# M8650D_cpld.net
KiCad netlist of a schematic drawn in EAGLE
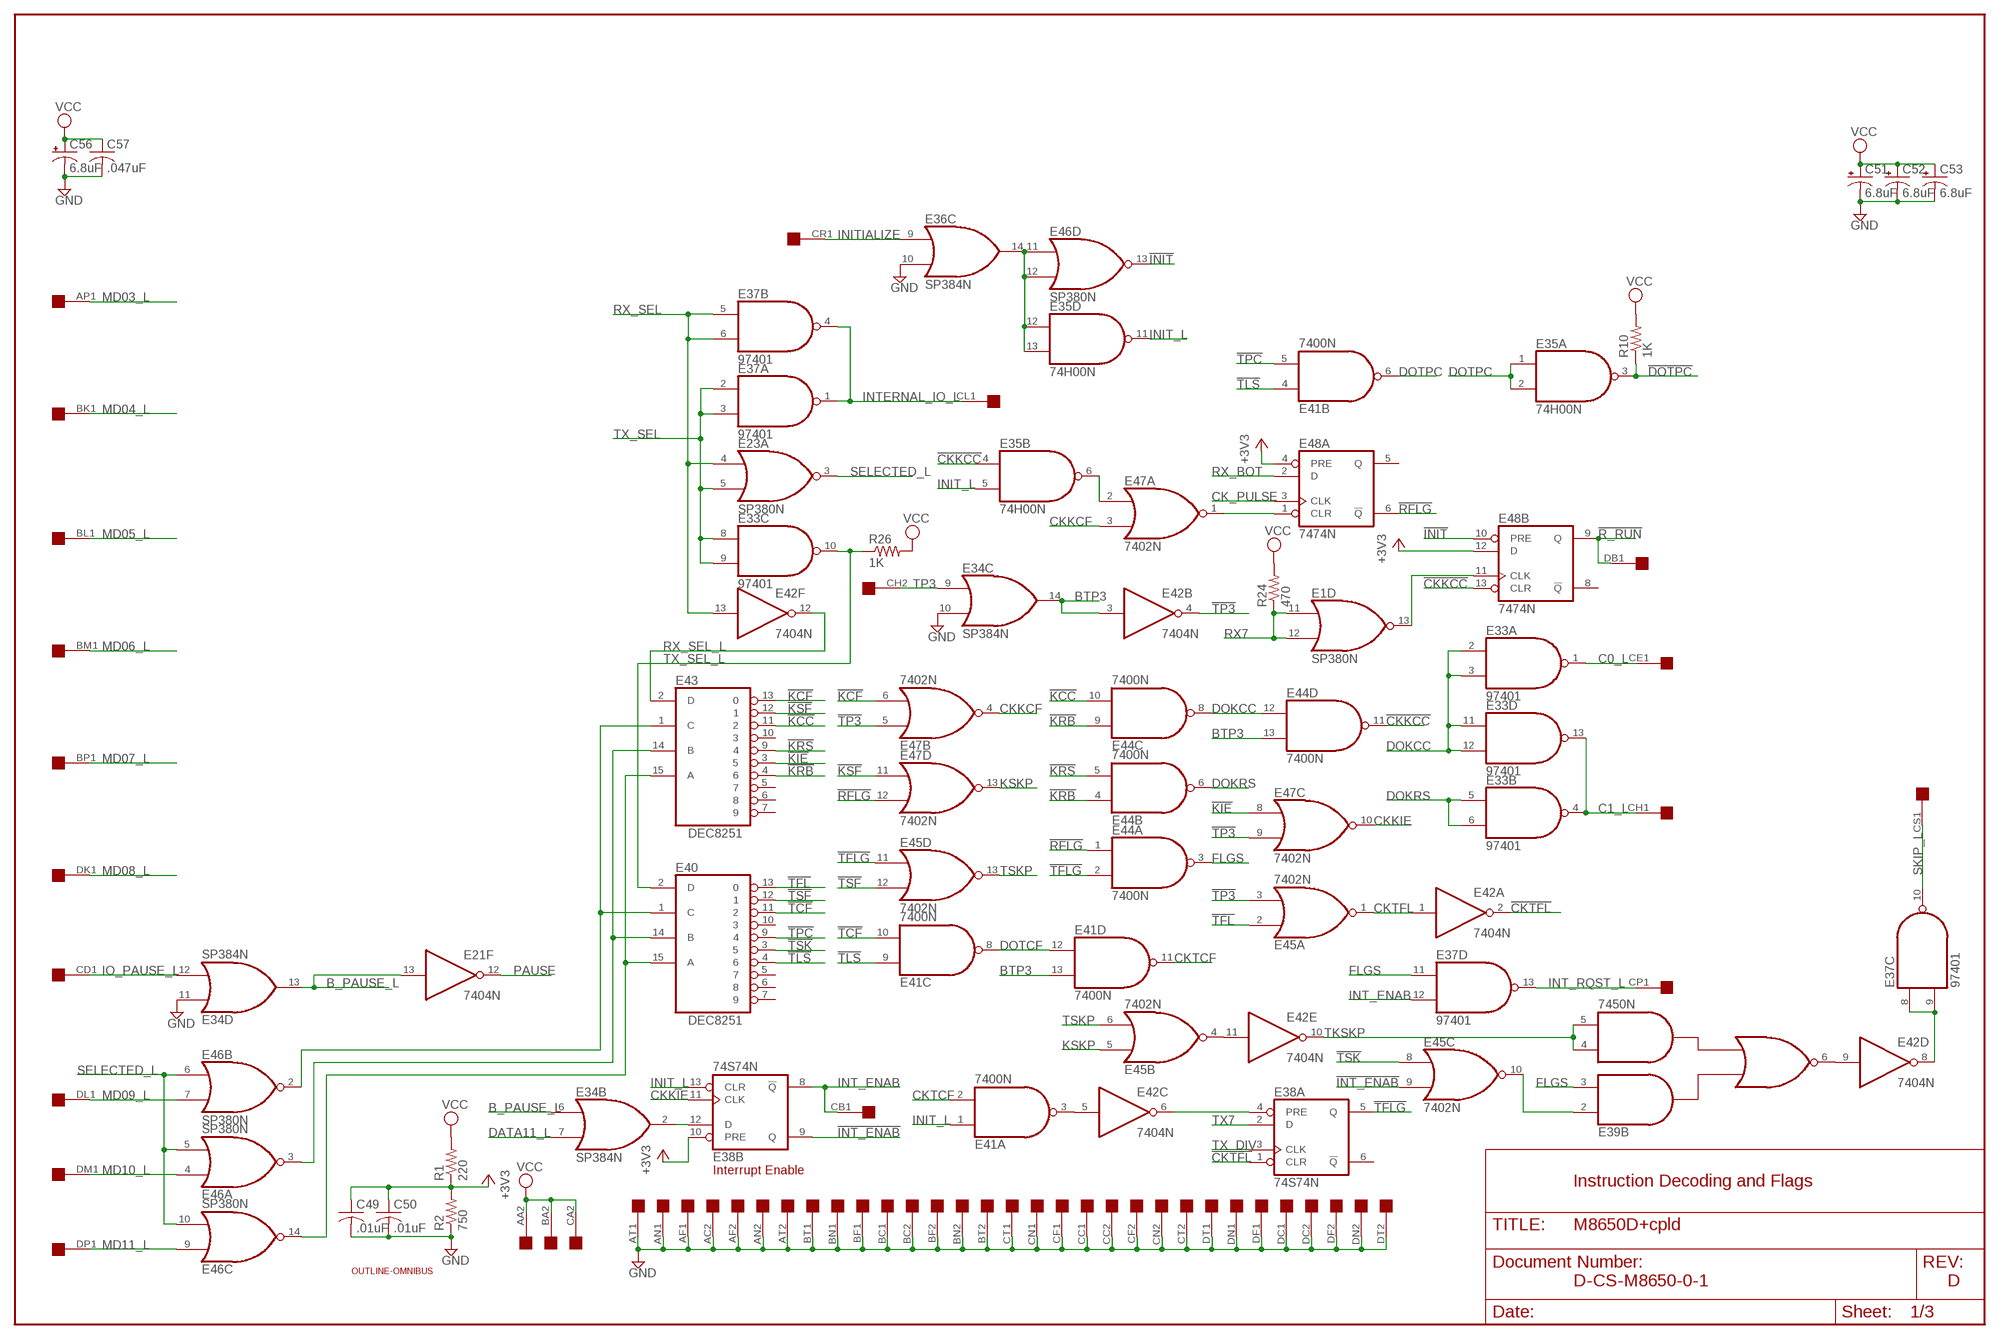
[diagram p0: schematic, sheet 1]
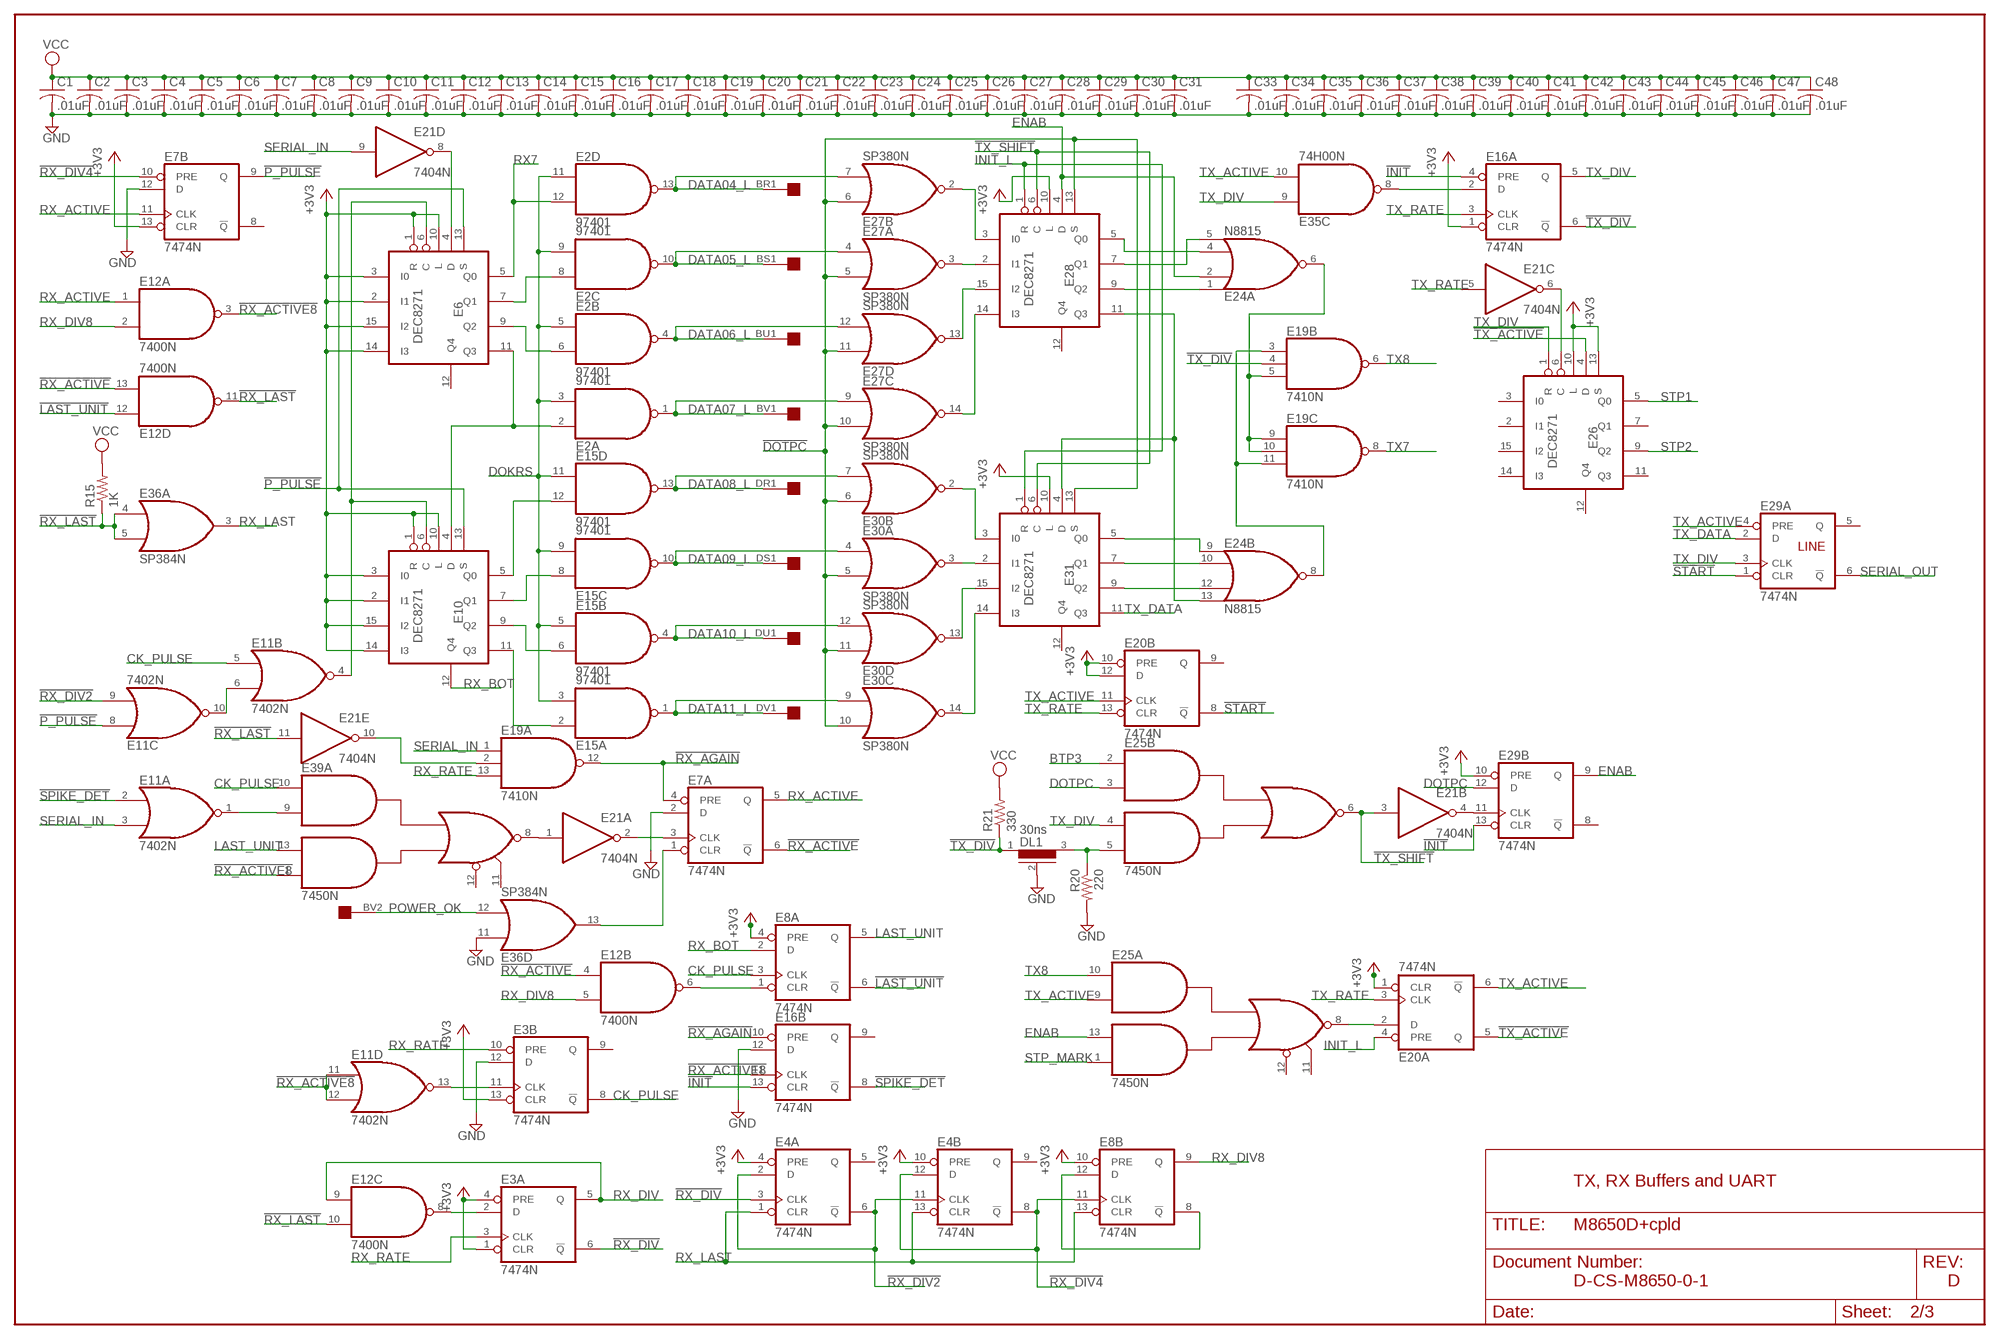
[diagram p1: schematic, sheet 2]
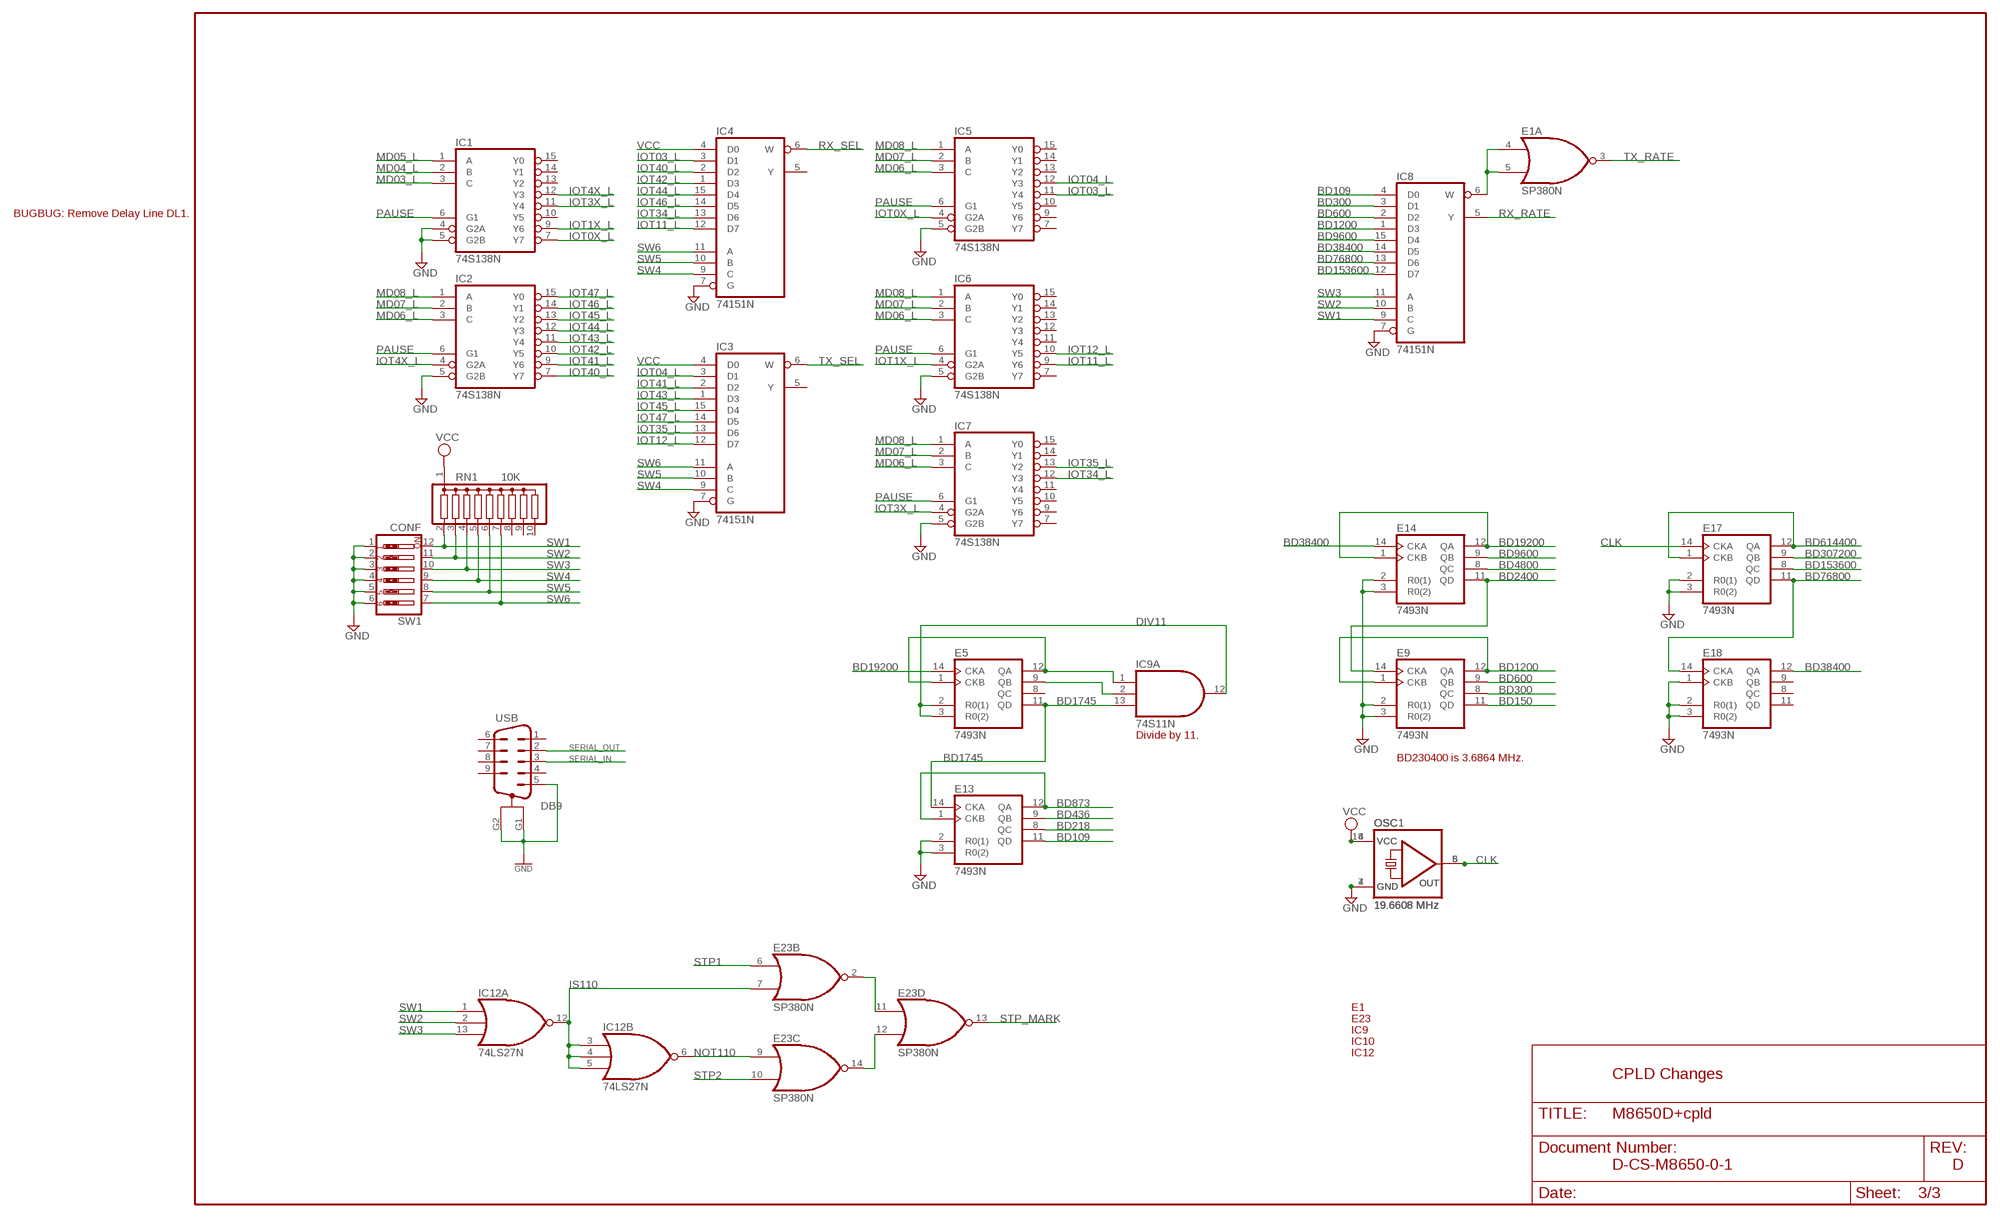
[diagram p2: schematic, sheet 3]

(export (version "E")
  (design (tool "Eeschema 10.0.6"))
  (components
    (comp (ref "E1")
      (value "SP380N")
      (footprint "eagle-import:DIL14")
      (libsource (lib "eagle-import") (part "SP380N"))
    )
    (comp (ref "E5")
      (value "7493N")
      (footprint "eagle-import:DIL14")
      (libsource (lib "eagle-import") (part "7493NLS"))
    )
    (comp (ref "E9")
      (value "7493N")
      (footprint "eagle-import:DIL14")
      (libsource (lib "eagle-import") (part "7493NLS"))
    )
    (comp (ref "E13")
      (value "7493N")
      (footprint "eagle-import:DIL14")
      (libsource (lib "eagle-import") (part "7493NLS"))
    )
    (comp (ref "E14")
      (value "7493N")
      (footprint "eagle-import:DIL14")
      (libsource (lib "eagle-import") (part "7493NLS"))
    )
    (comp (ref "E17")
      (value "7493N")
      (footprint "eagle-import:DIL14")
      (libsource (lib "eagle-import") (part "7493NLS"))
    )
    (comp (ref "E18")
      (value "7493N")
      (footprint "eagle-import:DIL14")
      (libsource (lib "eagle-import") (part "7493NLS"))
    )
    (comp (ref "E23")
      (value "SP380N")
      (footprint "eagle-import:DIL14")
      (libsource (lib "eagle-import") (part "SP380N"))
    )
    (comp (ref "IC1")
      (value "74S138N")
      (footprint "eagle-import:DIL16")
      (libsource (lib "eagle-import") (part "74138NS"))
    )
    (comp (ref "IC2")
      (value "74S138N")
      (footprint "eagle-import:DIL16")
      (libsource (lib "eagle-import") (part "74138NS"))
    )
    (comp (ref "IC3")
      (value "74151N")
      (footprint "eagle-import:DIL16")
      (libsource (lib "eagle-import") (part "74151NS"))
    )
    (comp (ref "IC4")
      (value "74151N")
      (footprint "eagle-import:DIL16")
      (libsource (lib "eagle-import") (part "74151NS"))
    )
    (comp (ref "IC5")
      (value "74S138N")
      (footprint "eagle-import:DIL16")
      (libsource (lib "eagle-import") (part "74138NS"))
    )
    (comp (ref "IC6")
      (value "74S138N")
      (footprint "eagle-import:DIL16")
      (libsource (lib "eagle-import") (part "74138NS"))
    )
    (comp (ref "IC7")
      (value "74S138N")
      (footprint "eagle-import:DIL16")
      (libsource (lib "eagle-import") (part "74138NS"))
    )
    (comp (ref "IC8")
      (value "74151N")
      (footprint "eagle-import:DIL16")
      (libsource (lib "eagle-import") (part "74151N"))
    )
    (comp (ref "IC9")
      (value "74S11N")
      (footprint "eagle-import:DIL14")
      (libsource (lib "eagle-import") (part "7411NS"))
    )
    (comp (ref "IC12")
      (value "74LS27N")
      (footprint "eagle-import:DIL14")
      (libsource (lib "eagle-import") (part "7427NLS"))
    )
    (comp (ref "OSC")
      (value "19.6608 MHz")
      (footprint "eagle-import:DIL08S")
      (libsource (lib "eagle-import") (part "QG5460"))
    )
    (comp (ref "OSC1")
      (value "19.6608 MHz")
      (footprint "eagle-import:DIL14S")
      (libsource (lib "eagle-import") (part "QG5860"))
    )
    (comp (ref "RN1")
      (value "10K")
      (footprint "eagle-import:SIL10")
      (libsource (lib "eagle-import") (part "G09R"))
    )
    (comp (ref "SW1")
      (value "CONF")
      (footprint "eagle-import:EDG-06")
      (libsource (lib "eagle-import") (part "SW_DIP-6"))
    )
    (comp (ref "USB")
      (value "DB9")
      (footprint "eagle-import:AMP_DB-9RA")
      (fields (field (name "MANF") "TE/AMP"))
      (libsource (lib "eagle-import") (part "DB9"))
    )
    (comp (ref "C49")
      (value ".01uF")
      (footprint "eagle-import:C050-025X075")
      (libsource (lib "eagle-import") (part "C-US050-025X075"))
    )
    (comp (ref "C50")
      (value ".01uF")
      (footprint "eagle-import:C050-025X075")
      (libsource (lib "eagle-import") (part "C-US050-025X075"))
    )
    (comp (ref "C51")
      (value "6.8uF")
      (footprint "eagle-import:E12-8")
      (libsource (lib "eagle-import") (part "CPOL-USE20-8AXIAL"))
    )
    (comp (ref "C52")
      (value "6.8uF")
      (footprint "eagle-import:E12-8")
      (libsource (lib "eagle-import") (part "CPOL-USE20-8AXIAL"))
    )
    (comp (ref "C53")
      (value "6.8uF")
      (footprint "eagle-import:E12-8")
      (libsource (lib "eagle-import") (part "CPOL-USE20-8AXIAL"))
    )
    (comp (ref "C56")
      (value "6.8uF")
      (footprint "eagle-import:E12-8")
      (libsource (lib "eagle-import") (part "CPOL-USE20-8AXIAL"))
    )
    (comp (ref "C57")
      (value ".047uF")
      (footprint "eagle-import:C050-025X075")
      (libsource (lib "eagle-import") (part "C-US050-025X075"))
    )
    (comp (ref "E21")
      (value "7404N")
      (footprint "eagle-import:DIL14")
      (libsource (lib "eagle-import") (part "7404N"))
    )
    (comp (ref "E33")
      (value "97401")
      (footprint "eagle-import:DIL14")
      (libsource (lib "eagle-import") (part "7401NLS"))
    )
    (comp (ref "E34")
      (value "SP384N")
      (footprint "eagle-import:DIL14")
      (libsource (lib "eagle-import") (part "SP384N"))
    )
    (comp (ref "E35")
      (value "74H00N")
      (footprint "eagle-import:DIL14")
      (libsource (lib "eagle-import") (part "7400N"))
    )
    (comp (ref "E36")
      (value "SP384N")
      (footprint "eagle-import:DIL14")
      (libsource (lib "eagle-import") (part "SP384N"))
    )
    (comp (ref "E37")
      (value "97401")
      (footprint "eagle-import:DIL14")
      (libsource (lib "eagle-import") (part "7401NLS"))
    )
    (comp (ref "E38")
      (value "74S74N")
      (footprint "eagle-import:DIL14")
      (libsource (lib "eagle-import") (part "7474NS"))
    )
    (comp (ref "E39")
      (value "7450N")
      (footprint "eagle-import:DIL14")
      (libsource (lib "eagle-import") (part "7450N"))
    )
    (comp (ref "E40")
      (value "DEC8251")
      (footprint "eagle-import:DIL16")
      (libsource (lib "eagle-import") (part "DEC8251"))
    )
    (comp (ref "E41")
      (value "7400N")
      (footprint "eagle-import:DIL14")
      (libsource (lib "eagle-import") (part "7400N"))
    )
    (comp (ref "E42")
      (value "7404N")
      (footprint "eagle-import:DIL14")
      (libsource (lib "eagle-import") (part "7404N"))
    )
    (comp (ref "E43")
      (value "DEC8251")
      (footprint "eagle-import:DIL16")
      (libsource (lib "eagle-import") (part "DEC8251"))
    )
    (comp (ref "E44")
      (value "7400N")
      (footprint "eagle-import:DIL14")
      (libsource (lib "eagle-import") (part "7400N"))
    )
    (comp (ref "E45")
      (value "7402N")
      (footprint "eagle-import:DIL14")
      (libsource (lib "eagle-import") (part "7402N"))
    )
    (comp (ref "E46")
      (value "SP380N")
      (footprint "eagle-import:DIL14")
      (libsource (lib "eagle-import") (part "SP380N"))
    )
    (comp (ref "E47")
      (value "7402N")
      (footprint "eagle-import:DIL14")
      (libsource (lib "eagle-import") (part "7402N"))
    )
    (comp (ref "E48")
      (value "7474N")
      (footprint "eagle-import:DIL14")
      (libsource (lib "eagle-import") (part "7474NS"))
    )
    (comp (ref "R1")
      (value "220")
      (footprint "eagle-import:0207_10")
      (libsource (lib "eagle-import") (part "R-US_0207/10"))
    )
    (comp (ref "R2")
      (value "750")
      (footprint "eagle-import:0207_10")
      (libsource (lib "eagle-import") (part "R-US_0207/10"))
    )
    (comp (ref "R10")
      (value "1K")
      (footprint "eagle-import:0207_10")
      (libsource (lib "eagle-import") (part "R-US_0207/10"))
    )
    (comp (ref "R24")
      (value "470")
      (footprint "eagle-import:0207_10")
      (libsource (lib "eagle-import") (part "R-US_0207/10"))
    )
    (comp (ref "R26")
      (value "1K")
      (footprint "eagle-import:0207_10")
      (libsource (lib "eagle-import") (part "R-US_0207/10"))
    )
    (comp (ref "U$1")
      (value "OUTLINE-OMNIBUS")
      (footprint "eagle-import:OMNIBUS")
      (libsource (lib "eagle-import") (part "OUTLINE-OMNIBUS"))
    )
    (comp (ref "U$2")
      (value "OMNIBUS")
      (footprint "eagle-import:EDGE-CON8")
      (libsource (lib "eagle-import") (part "QUAD"))
    )
    (comp (ref "C1")
      (value ".01uF")
      (footprint "eagle-import:C050-025X075")
      (libsource (lib "eagle-import") (part "C-US050-025X075"))
    )
    (comp (ref "C2")
      (value ".01uF")
      (footprint "eagle-import:C050-025X075")
      (libsource (lib "eagle-import") (part "C-US050-025X075"))
    )
    (comp (ref "C3")
      (value ".01uF")
      (footprint "eagle-import:C050-025X075")
      (libsource (lib "eagle-import") (part "C-US050-025X075"))
    )
    (comp (ref "C4")
      (value ".01uF")
      (footprint "eagle-import:C050-025X075")
      (libsource (lib "eagle-import") (part "C-US050-025X075"))
    )
    (comp (ref "C5")
      (value ".01uF")
      (footprint "eagle-import:C050-025X075")
      (libsource (lib "eagle-import") (part "C-US050-025X075"))
    )
    (comp (ref "C6")
      (value ".01uF")
      (footprint "eagle-import:C050-025X075")
      (libsource (lib "eagle-import") (part "C-US050-025X075"))
    )
    (comp (ref "C7")
      (value ".01uF")
      (footprint "eagle-import:C050-025X075")
      (libsource (lib "eagle-import") (part "C-US050-025X075"))
    )
    (comp (ref "C8")
      (value ".01uF")
      (footprint "eagle-import:C050-025X075")
      (libsource (lib "eagle-import") (part "C-US050-025X075"))
    )
    (comp (ref "C9")
      (value ".01uF")
      (footprint "eagle-import:C050-025X075")
      (libsource (lib "eagle-import") (part "C-US050-025X075"))
    )
    (comp (ref "C10")
      (value ".01uF")
      (footprint "eagle-import:C050-025X075")
      (libsource (lib "eagle-import") (part "C-US050-025X075"))
    )
    (comp (ref "C11")
      (value ".01uF")
      (footprint "eagle-import:C050-025X075")
      (libsource (lib "eagle-import") (part "C-US050-025X075"))
    )
    (comp (ref "C12")
      (value ".01uF")
      (footprint "eagle-import:C050-025X075")
      (libsource (lib "eagle-import") (part "C-US050-025X075"))
    )
    (comp (ref "C13")
      (value ".01uF")
      (footprint "eagle-import:C050-025X075")
      (libsource (lib "eagle-import") (part "C-US050-025X075"))
    )
    (comp (ref "C14")
      (value ".01uF")
      (footprint "eagle-import:C050-025X075")
      (libsource (lib "eagle-import") (part "C-US050-025X075"))
    )
    (comp (ref "C15")
      (value ".01uF")
      (footprint "eagle-import:C050-025X075")
      (libsource (lib "eagle-import") (part "C-US050-025X075"))
    )
    (comp (ref "C16")
      (value ".01uF")
      (footprint "eagle-import:C050-025X075")
      (libsource (lib "eagle-import") (part "C-US050-025X075"))
    )
    (comp (ref "C17")
      (value ".01uF")
      (footprint "eagle-import:C050-025X075")
      (libsource (lib "eagle-import") (part "C-US050-025X075"))
    )
    (comp (ref "C18")
      (value ".01uF")
      (footprint "eagle-import:C050-025X075")
      (libsource (lib "eagle-import") (part "C-US050-025X075"))
    )
    (comp (ref "C19")
      (value ".01uF")
      (footprint "eagle-import:C050-025X075")
      (libsource (lib "eagle-import") (part "C-US050-025X075"))
    )
    (comp (ref "C20")
      (value ".01uF")
      (footprint "eagle-import:C050-025X075")
      (libsource (lib "eagle-import") (part "C-US050-025X075"))
    )
    (comp (ref "C21")
      (value ".01uF")
      (footprint "eagle-import:C050-025X075")
      (libsource (lib "eagle-import") (part "C-US050-025X075"))
    )
    (comp (ref "C22")
      (value ".01uF")
      (footprint "eagle-import:C050-025X075")
      (libsource (lib "eagle-import") (part "C-US050-025X075"))
    )
    (comp (ref "C23")
      (value ".01uF")
      (footprint "eagle-import:C050-025X075")
      (libsource (lib "eagle-import") (part "C-US050-025X075"))
    )
    (comp (ref "C24")
      (value ".01uF")
      (footprint "eagle-import:C050-025X075")
      (libsource (lib "eagle-import") (part "C-US050-025X075"))
    )
    (comp (ref "C25")
      (value ".01uF")
      (footprint "eagle-import:C050-025X075")
      (libsource (lib "eagle-import") (part "C-US050-025X075"))
    )
    (comp (ref "C26")
      (value ".01uF")
      (footprint "eagle-import:C050-025X075")
      (libsource (lib "eagle-import") (part "C-US050-025X075"))
    )
    (comp (ref "C27")
      (value ".01uF")
      (footprint "eagle-import:C050-025X075")
      (libsource (lib "eagle-import") (part "C-US050-025X075"))
    )
    (comp (ref "C28")
      (value ".01uF")
      (footprint "eagle-import:C050-025X075")
      (libsource (lib "eagle-import") (part "C-US050-025X075"))
    )
    (comp (ref "C29")
      (value ".01uF")
      (footprint "eagle-import:C050-025X075")
      (libsource (lib "eagle-import") (part "C-US050-025X075"))
    )
    (comp (ref "C30")
      (value ".01uF")
      (footprint "eagle-import:C050-025X075")
      (libsource (lib "eagle-import") (part "C-US050-025X075"))
    )
    (comp (ref "C31")
      (value ".01uF")
      (footprint "eagle-import:C050-025X075")
      (libsource (lib "eagle-import") (part "C-US050-025X075"))
    )
    (comp (ref "C33")
      (value ".01uF")
      (footprint "eagle-import:C050-025X075")
      (libsource (lib "eagle-import") (part "C-US050-025X075"))
    )
    (comp (ref "C34")
      (value ".01uF")
      (footprint "eagle-import:C050-025X075")
      (libsource (lib "eagle-import") (part "C-US050-025X075"))
    )
    (comp (ref "C35")
      (value ".01uF")
      (footprint "eagle-import:C050-025X075")
      (libsource (lib "eagle-import") (part "C-US050-025X075"))
    )
    (comp (ref "C36")
      (value ".01uF")
      (footprint "eagle-import:C050-025X075")
      (libsource (lib "eagle-import") (part "C-US050-025X075"))
    )
    (comp (ref "C37")
      (value ".01uF")
      (footprint "eagle-import:C050-025X075")
      (libsource (lib "eagle-import") (part "C-US050-025X075"))
    )
    (comp (ref "C38")
      (value ".01uF")
      (footprint "eagle-import:C050-025X075")
      (libsource (lib "eagle-import") (part "C-US050-025X075"))
    )
    (comp (ref "C39")
      (value ".01uF")
      (footprint "eagle-import:C050-025X075")
      (libsource (lib "eagle-import") (part "C-US050-025X075"))
    )
    (comp (ref "C40")
      (value ".01uF")
      (footprint "eagle-import:C050-025X075")
      (libsource (lib "eagle-import") (part "C-US050-025X075"))
    )
    (comp (ref "C41")
      (value ".01uF")
      (footprint "eagle-import:C050-025X075")
      (libsource (lib "eagle-import") (part "C-US050-025X075"))
    )
    (comp (ref "C42")
      (value ".01uF")
      (footprint "eagle-import:C050-025X075")
      (libsource (lib "eagle-import") (part "C-US050-025X075"))
    )
    (comp (ref "C43")
      (value ".01uF")
      (footprint "eagle-import:C050-025X075")
      (libsource (lib "eagle-import") (part "C-US050-025X075"))
    )
    (comp (ref "C44")
      (value ".01uF")
      (footprint "eagle-import:C050-025X075")
      (libsource (lib "eagle-import") (part "C-US050-025X075"))
    )
    (comp (ref "C45")
      (value ".01uF")
      (footprint "eagle-import:C050-025X075")
      (libsource (lib "eagle-import") (part "C-US050-025X075"))
    )
    (comp (ref "C46")
      (value ".01uF")
      (footprint "eagle-import:C050-025X075")
      (libsource (lib "eagle-import") (part "C-US050-025X075"))
    )
    (comp (ref "C47")
      (value ".01uF")
      (footprint "eagle-import:C050-025X075")
      (libsource (lib "eagle-import") (part "C-US050-025X075"))
    )
    (comp (ref "C48")
      (value ".01uF")
      (footprint "eagle-import:C050-025X075")
      (libsource (lib "eagle-import") (part "C-US050-025X075"))
    )
    (comp (ref "DL1")
      (value "30ns")
      (footprint "eagle-import:RCL-L-00-05")
      (libsource (lib "eagle-import") (part "RCL-L-00-05"))
    )
    (comp (ref "E2")
      (value "97401")
      (footprint "eagle-import:DIL14")
      (libsource (lib "eagle-import") (part "7401NLS"))
    )
    (comp (ref "E3")
      (value "7474N")
      (footprint "eagle-import:DIL14")
      (libsource (lib "eagle-import") (part "7474NS"))
    )
    (comp (ref "E4")
      (value "7474N")
      (footprint "eagle-import:DIL14")
      (libsource (lib "eagle-import") (part "7474NS"))
    )
    (comp (ref "E6")
      (value "DEC8271")
      (footprint "eagle-import:DIL16")
      (libsource (lib "eagle-import") (part "DEC8271"))
    )
    (comp (ref "E7")
      (value "7474N")
      (footprint "eagle-import:DIL14")
      (libsource (lib "eagle-import") (part "7474NS"))
    )
    (comp (ref "E8")
      (value "7474N")
      (footprint "eagle-import:DIL14")
      (libsource (lib "eagle-import") (part "7474NS"))
    )
    (comp (ref "E10")
      (value "DEC8271")
      (footprint "eagle-import:DIL16")
      (libsource (lib "eagle-import") (part "DEC8271"))
    )
    (comp (ref "E11")
      (value "7402N")
      (footprint "eagle-import:DIL14")
      (libsource (lib "eagle-import") (part "7402N"))
    )
    (comp (ref "E12")
      (value "7400N")
      (footprint "eagle-import:DIL14")
      (libsource (lib "eagle-import") (part "7400N"))
    )
    (comp (ref "E15")
      (value "97401")
      (footprint "eagle-import:DIL14")
      (libsource (lib "eagle-import") (part "7401NLS"))
    )
    (comp (ref "E16")
      (value "7474N")
      (footprint "eagle-import:DIL14")
      (libsource (lib "eagle-import") (part "7474NS"))
    )
    (comp (ref "E19")
      (value "7410N")
      (footprint "eagle-import:DIL14")
      (libsource (lib "eagle-import") (part "7410N"))
    )
    (comp (ref "E20")
      (value "7474N")
      (footprint "eagle-import:DIL14")
      (libsource (lib "eagle-import") (part "7474NS"))
    )
    (comp (ref "E24")
      (value "N8815")
      (footprint "eagle-import:DIL14")
      (libsource (lib "eagle-import") (part "N8815"))
    )
    (comp (ref "E25")
      (value "7450N")
      (footprint "eagle-import:DIL14")
      (libsource (lib "eagle-import") (part "7450N"))
    )
    (comp (ref "E26")
      (value "DEC8271")
      (footprint "eagle-import:DIL16")
      (libsource (lib "eagle-import") (part "DEC8271"))
    )
    (comp (ref "E27")
      (value "SP380N")
      (footprint "eagle-import:DIL14")
      (libsource (lib "eagle-import") (part "SP380N"))
    )
    (comp (ref "E28")
      (value "DEC8271")
      (footprint "eagle-import:DIL16")
      (libsource (lib "eagle-import") (part "DEC8271"))
    )
    (comp (ref "E29")
      (value "7474N")
      (footprint "eagle-import:DIL14")
      (libsource (lib "eagle-import") (part "7474NS"))
    )
    (comp (ref "E30")
      (value "SP380N")
      (footprint "eagle-import:DIL14")
      (libsource (lib "eagle-import") (part "SP380N"))
    )
    (comp (ref "E31")
      (value "DEC8271")
      (footprint "eagle-import:DIL16")
      (libsource (lib "eagle-import") (part "DEC8271"))
    )
    (comp (ref "R15")
      (value "1K")
      (footprint "eagle-import:0207_10")
      (libsource (lib "eagle-import") (part "R-US_0207/10"))
    )
    (comp (ref "R20")
      (value "220")
      (footprint "eagle-import:0207_10")
      (libsource (lib "eagle-import") (part "R-US_0207/10"))
    )
    (comp (ref "R21")
      (value "330")
      (footprint "eagle-import:0207_10")
      (libsource (lib "eagle-import") (part "R-US_0207/10"))
    )
  )
  (nets
    (net (code "1") (name "+3V3") (class "Default")
      (node (ref "C49") (pin "1") (pinfunction "1_1") (pintype "passive"))
      (node (ref "C50") (pin "1") (pinfunction "1_1") (pintype "passive"))
      (node (ref "E10") (pin "1") (pinfunction "R_1") (pintype "input"))
      (node (ref "E10") (pin "10") (pinfunction "L_10") (pintype "input"))
      (node (ref "E10") (pin "14") (pinfunction "I3_14") (pintype "input"))
      (node (ref "E10") (pin "15") (pinfunction "I2_15") (pintype "input"))
      (node (ref "E10") (pin "2") (pinfunction "I1_2") (pintype "input"))
      (node (ref "E10") (pin "3") (pinfunction "I0_3") (pintype "input"))
      (node (ref "E16") (pin "1") (pinfunction "CLR_1") (pintype "input"))
      (node (ref "E20") (pin "1") (pinfunction "CLR_1") (pintype "input"))
      (node (ref "E20") (pin "10") (pinfunction "PRE_10") (pintype "input"))
      (node (ref "E20") (pin "12") (pinfunction "D_12") (pintype "input"))
      (node (ref "E26") (pin "10") (pinfunction "L_10") (pintype "input"))
      (node (ref "E26") (pin "13") (pinfunction "S_13") (pintype "input"))
      (node (ref "E28") (pin "10") (pinfunction "L_10") (pintype "input"))
      (node (ref "E29") (pin "10") (pinfunction "PRE_10") (pintype "input"))
      (node (ref "E3") (pin "1") (pinfunction "CLR_1") (pintype "input"))
      (node (ref "E3") (pin "13") (pinfunction "CLR_13") (pintype "input"))
      (node (ref "E3") (pin "4") (pinfunction "PRE_4") (pintype "input"))
      (node (ref "E31") (pin "10") (pinfunction "L_10") (pintype "input"))
      (node (ref "E38") (pin "10") (pinfunction "PRE_10") (pintype "input"))
      (node (ref "E4") (pin "10") (pinfunction "PRE_10") (pintype "input"))
      (node (ref "E4") (pin "4") (pinfunction "PRE_4") (pintype "input"))
      (node (ref "E48") (pin "12") (pinfunction "D_12") (pintype "input"))
      (node (ref "E48") (pin "4") (pinfunction "PRE_4") (pintype "input"))
      (node (ref "E6") (pin "1") (pinfunction "R_1") (pintype "input"))
      (node (ref "E6") (pin "10") (pinfunction "L_10") (pintype "input"))
      (node (ref "E6") (pin "14") (pinfunction "I3_14") (pintype "input"))
      (node (ref "E6") (pin "15") (pinfunction "I2_15") (pintype "input"))
      (node (ref "E6") (pin "2") (pinfunction "I1_2") (pintype "input"))
      (node (ref "E6") (pin "3") (pinfunction "I0_3") (pintype "input"))
      (node (ref "E7") (pin "13") (pinfunction "CLR_13") (pintype "input"))
      (node (ref "E8") (pin "10") (pinfunction "PRE_10") (pintype "input"))
      (node (ref "E8") (pin "4") (pinfunction "PRE_4") (pintype "input"))
      (node (ref "R1") (pin "1") (pinfunction "1_1") (pintype "passive"))
      (node (ref "R2") (pin "2") (pinfunction "2_2") (pintype "passive"))
    )
    (net (code "2") (name "BD109") (class "Default")
      (node (ref "E13") (pin "11") (pinfunction "QD_11") (pintype "output"))
      (node (ref "IC8") (pin "4") (pinfunction "D0_4") (pintype "input"))
    )
    (net (code "3") (name "BD150") (class "Default")
      (node (ref "E9") (pin "11") (pinfunction "QD_11") (pintype "output"))
    )
    (net (code "4") (name "BD218") (class "Default")
      (node (ref "E13") (pin "8") (pinfunction "QC_8") (pintype "output"))
    )
    (net (code "5") (name "BD300") (class "Default")
      (node (ref "E9") (pin "8") (pinfunction "QC_8") (pintype "output"))
      (node (ref "IC8") (pin "3") (pinfunction "D1_3") (pintype "input"))
    )
    (net (code "6") (name "BD436") (class "Default")
      (node (ref "E13") (pin "9") (pinfunction "QB_9") (pintype "output"))
    )
    (net (code "7") (name "BD600") (class "Default")
      (node (ref "E9") (pin "9") (pinfunction "QB_9") (pintype "output"))
      (node (ref "IC8") (pin "2") (pinfunction "D2_2") (pintype "input"))
    )
    (net (code "8") (name "BD873") (class "Default")
      (node (ref "E13") (pin "1") (pinfunction "CKB_1") (pintype "input"))
      (node (ref "E13") (pin "12") (pinfunction "QA_12") (pintype "output"))
    )
    (net (code "9") (name "BD1200") (class "Default")
      (node (ref "E9") (pin "1") (pinfunction "CKB_1") (pintype "input"))
      (node (ref "E9") (pin "12") (pinfunction "QA_12") (pintype "output"))
      (node (ref "IC8") (pin "1") (pinfunction "D3_1") (pintype "input"))
    )
    (net (code "10") (name "BD1745") (class "Default")
      (node (ref "E13") (pin "14") (pinfunction "CKA_14") (pintype "input"))
      (node (ref "E5") (pin "11") (pinfunction "QD_11") (pintype "output"))
      (node (ref "IC9") (pin "13") (pinfunction "I2_13") (pintype "input"))
    )
    (net (code "11") (name "BD2400") (class "Default")
      (node (ref "E14") (pin "11") (pinfunction "QD_11") (pintype "output"))
      (node (ref "E9") (pin "14") (pinfunction "CKA_14") (pintype "input"))
    )
    (net (code "12") (name "BD4800") (class "Default")
      (node (ref "E14") (pin "8") (pinfunction "QC_8") (pintype "output"))
    )
    (net (code "13") (name "BD9600") (class "Default")
      (node (ref "E14") (pin "9") (pinfunction "QB_9") (pintype "output"))
      (node (ref "IC8") (pin "15") (pinfunction "D4_15") (pintype "input"))
    )
    (net (code "14") (name "BD19200") (class "Default")
      (node (ref "E14") (pin "1") (pinfunction "CKB_1") (pintype "input"))
      (node (ref "E14") (pin "12") (pinfunction "QA_12") (pintype "output"))
      (node (ref "E5") (pin "14") (pinfunction "CKA_14") (pintype "input"))
    )
    (net (code "15") (name "BD38400") (class "Default")
      (node (ref "E14") (pin "14") (pinfunction "CKA_14") (pintype "input"))
      (node (ref "E18") (pin "12") (pinfunction "QA_12") (pintype "output"))
      (node (ref "IC8") (pin "14") (pinfunction "D5_14") (pintype "input"))
    )
    (net (code "16") (name "BD76800") (class "Default")
      (node (ref "E17") (pin "11") (pinfunction "QD_11") (pintype "output"))
      (node (ref "E18") (pin "14") (pinfunction "CKA_14") (pintype "input"))
      (node (ref "IC8") (pin "13") (pinfunction "D6_13") (pintype "input"))
    )
    (net (code "17") (name "BD153600") (class "Default")
      (node (ref "E17") (pin "8") (pinfunction "QC_8") (pintype "output"))
      (node (ref "IC8") (pin "12") (pinfunction "D7_12") (pintype "input"))
    )
    (net (code "18") (name "BD307200") (class "Default")
      (node (ref "E17") (pin "9") (pinfunction "QB_9") (pintype "output"))
    )
    (net (code "19") (name "BD614400") (class "Default")
      (node (ref "E17") (pin "1") (pinfunction "CKB_1") (pintype "input"))
      (node (ref "E17") (pin "12") (pinfunction "QA_12") (pintype "output"))
    )
    (net (code "20") (name "BTP3") (class "Default")
      (node (ref "E25") (pin "2") (pinfunction "I1_2") (pintype "input"))
      (node (ref "E34") (pin "14") (pinfunction "O_14") (pintype "output"))
      (node (ref "E41") (pin "13") (pinfunction "I1_13") (pintype "input"))
      (node (ref "E42") (pin "3") (pinfunction "I_3") (pintype "input"))
      (node (ref "E44") (pin "13") (pinfunction "I1_13") (pintype "input"))
    )
    (net (code "21") (name "B_PAUSE_L") (class "Default")
      (node (ref "E21") (pin "13") (pinfunction "I_13") (pintype "input"))
      (node (ref "E34") (pin "13") (pinfunction "O_13") (pintype "output"))
      (node (ref "E34") (pin "6") (pinfunction "I0_6") (pintype "input"))
    )
    (net (code "22") (name "C0_L") (class "Default")
      (node (ref "E33") (pin "1") (pinfunction "O_1") (pintype "open_collector"))
      (node (ref "U$2") (pin "CE1") (pinfunction "1_CE1") (pintype "bidirectional"))
    )
    (net (code "23") (name "C1_L") (class "Default")
      (node (ref "E33") (pin "13") (pinfunction "O_13") (pintype "open_collector"))
      (node (ref "E33") (pin "4") (pinfunction "O_4") (pintype "open_collector"))
      (node (ref "U$2") (pin "CH1") (pinfunction "1_CH1") (pintype "bidirectional"))
    )
    (net (code "24") (name "CKKCF") (class "Default")
      (node (ref "E47") (pin "3") (pinfunction "I1_3") (pintype "input"))
      (node (ref "E47") (pin "4") (pinfunction "O_4") (pintype "output"))
    )
    (net (code "25") (name "CKKIE") (class "Default")
      (node (ref "E38") (pin "11") (pinfunction "CLK_11") (pintype "input"))
      (node (ref "E47") (pin "10") (pinfunction "O_10") (pintype "output"))
    )
    (net (code "26") (name "CKTCF") (class "Default")
      (node (ref "E41") (pin "11") (pinfunction "O_11") (pintype "output"))
      (node (ref "E41") (pin "2") (pinfunction "I1_2") (pintype "input"))
    )
    (net (code "27") (name "CKTFL") (class "Default")
      (node (ref "E42") (pin "1") (pinfunction "I_1") (pintype "input"))
      (node (ref "E45") (pin "1") (pinfunction "O_1") (pintype "output"))
    )
    (net (code "28") (name "CK_PULSE") (class "Default")
      (node (ref "E11") (pin "5") (pinfunction "I0_5") (pintype "input"))
      (node (ref "E3") (pin "8") (pinfunction "~{Q}_8") (pintype "output"))
      (node (ref "E39") (pin "10") (pinfunction "I1_10") (pintype "input"))
      (node (ref "E48") (pin "3") (pinfunction "CLK_3") (pintype "input"))
      (node (ref "E8") (pin "3") (pinfunction "CLK_3") (pintype "input"))
    )
    (net (code "29") (name "CLK") (class "Default")
      (node (ref "E17") (pin "14") (pinfunction "CKA_14") (pintype "input"))
      (node (ref "OSC") (pin "5") (pinfunction "OUT_5") (pintype "output"))
      (node (ref "OSC1") (pin "8") (pinfunction "OUT_8") (pintype "output"))
    )
    (net (code "30") (name "DATA04_L") (class "Default")
      (node (ref "E2") (pin "13") (pinfunction "O_13") (pintype "open_collector"))
      (node (ref "E27") (pin "7") (pinfunction "I1_7") (pintype "input"))
      (node (ref "U$2") (pin "BR1") (pinfunction "1_BR1") (pintype "bidirectional"))
    )
    (net (code "31") (name "DATA05_L") (class "Default")
      (node (ref "E2") (pin "10") (pinfunction "O_10") (pintype "open_collector"))
      (node (ref "E27") (pin "4") (pinfunction "I0_4") (pintype "input"))
      (node (ref "U$2") (pin "BS1") (pinfunction "1_BS1") (pintype "bidirectional"))
    )
    (net (code "32") (name "DATA06_L") (class "Default")
      (node (ref "E2") (pin "4") (pinfunction "O_4") (pintype "open_collector"))
      (node (ref "E27") (pin "12") (pinfunction "I1_12") (pintype "input"))
      (node (ref "U$2") (pin "BU1") (pinfunction "1_BU1") (pintype "bidirectional"))
    )
    (net (code "33") (name "DATA07_L") (class "Default")
      (node (ref "E2") (pin "1") (pinfunction "O_1") (pintype "open_collector"))
      (node (ref "E27") (pin "9") (pinfunction "I0_9") (pintype "input"))
      (node (ref "U$2") (pin "BV1") (pinfunction "1_BV1") (pintype "bidirectional"))
    )
    (net (code "34") (name "DATA08_L") (class "Default")
      (node (ref "E15") (pin "13") (pinfunction "O_13") (pintype "open_collector"))
      (node (ref "E30") (pin "7") (pinfunction "I1_7") (pintype "input"))
      (node (ref "U$2") (pin "DR1") (pinfunction "1_DR1") (pintype "bidirectional"))
    )
    (net (code "35") (name "DATA09_L") (class "Default")
      (node (ref "E15") (pin "10") (pinfunction "O_10") (pintype "open_collector"))
      (node (ref "E30") (pin "4") (pinfunction "I0_4") (pintype "input"))
      (node (ref "U$2") (pin "DS1") (pinfunction "1_DS1") (pintype "bidirectional"))
    )
    (net (code "36") (name "DATA10_L") (class "Default")
      (node (ref "E15") (pin "4") (pinfunction "O_4") (pintype "open_collector"))
      (node (ref "E30") (pin "12") (pinfunction "I1_12") (pintype "input"))
      (node (ref "U$2") (pin "DU1") (pinfunction "1_DU1") (pintype "bidirectional"))
    )
    (net (code "37") (name "DATA11_L") (class "Default")
      (node (ref "E15") (pin "1") (pinfunction "O_1") (pintype "open_collector"))
      (node (ref "E30") (pin "9") (pinfunction "I0_9") (pintype "input"))
      (node (ref "E34") (pin "7") (pinfunction "I1_7") (pintype "input"))
      (node (ref "U$2") (pin "DV1") (pinfunction "1_DV1") (pintype "bidirectional"))
    )
    (net (code "38") (name "DIV11") (class "Default")
      (node (ref "E5") (pin "2") (pinfunction "R0(1)_2") (pintype "input"))
      (node (ref "E5") (pin "3") (pinfunction "R0(2)_3") (pintype "input"))
      (node (ref "IC9") (pin "12") (pinfunction "O_12") (pintype "output"))
    )
    (net (code "39") (name "DOKCC") (class "Default")
      (node (ref "E33") (pin "11") (pinfunction "I0_11") (pintype "input"))
      (node (ref "E33") (pin "12") (pinfunction "I1_12") (pintype "input"))
      (node (ref "E33") (pin "2") (pinfunction "I0_2") (pintype "input"))
      (node (ref "E33") (pin "3") (pinfunction "I1_3") (pintype "input"))
      (node (ref "E44") (pin "12") (pinfunction "I0_12") (pintype "input"))
      (node (ref "E44") (pin "8") (pinfunction "O_8") (pintype "output"))
    )
    (net (code "40") (name "DOKRS") (class "Default")
      (node (ref "E15") (pin "11") (pinfunction "I0_11") (pintype "input"))
      (node (ref "E15") (pin "3") (pinfunction "I1_3") (pintype "input"))
      (node (ref "E15") (pin "5") (pinfunction "I0_5") (pintype "input"))
      (node (ref "E15") (pin "9") (pinfunction "I1_9") (pintype "input"))
      (node (ref "E2") (pin "11") (pinfunction "I0_11") (pintype "input"))
      (node (ref "E2") (pin "3") (pinfunction "I1_3") (pintype "input"))
      (node (ref "E2") (pin "5") (pinfunction "I0_5") (pintype "input"))
      (node (ref "E2") (pin "9") (pinfunction "I1_9") (pintype "input"))
      (node (ref "E33") (pin "5") (pinfunction "I0_5") (pintype "input"))
      (node (ref "E33") (pin "6") (pinfunction "I1_6") (pintype "input"))
      (node (ref "E44") (pin "6") (pinfunction "O_6") (pintype "output"))
    )
    (net (code "41") (name "DOTCF") (class "Default")
      (node (ref "E41") (pin "12") (pinfunction "I0_12") (pintype "input"))
      (node (ref "E41") (pin "8") (pinfunction "O_8") (pintype "output"))
    )
    (net (code "42") (name "DOTPC") (class "Default")
      (node (ref "E25") (pin "3") (pinfunction "I2_3") (pintype "input"))
      (node (ref "E29") (pin "12") (pinfunction "D_12") (pintype "input"))
      (node (ref "E35") (pin "1") (pinfunction "I0_1") (pintype "input"))
      (node (ref "E35") (pin "2") (pinfunction "I1_2") (pintype "input"))
      (node (ref "E41") (pin "6") (pinfunction "O_6") (pintype "output"))
    )
    (net (code "43") (name "ENAB") (class "Default")
      (node (ref "E24") (pin "2") (pinfunction "I1_2") (pintype "input"))
      (node (ref "E25") (pin "13") (pinfunction "I3_13") (pintype "input"))
      (node (ref "E28") (pin "4") (pinfunction "D_4") (pintype "input"))
      (node (ref "E29") (pin "9") (pinfunction "Q_9") (pintype "output"))
    )
    (net (code "44") (name "FLGS") (class "Default")
      (node (ref "E37") (pin "11") (pinfunction "I0_11") (pintype "input"))
      (node (ref "E39") (pin "3") (pinfunction "I2_3") (pintype "input"))
      (node (ref "E44") (pin "3") (pinfunction "O_3") (pintype "output"))
    )
    (net (code "45") (name "GND") (class "Default")
      (node (ref "C1") (pin "2") (pinfunction "2_2") (pintype "passive"))
      (node (ref "C10") (pin "2") (pinfunction "2_2") (pintype "passive"))
      (node (ref "C11") (pin "2") (pinfunction "2_2") (pintype "passive"))
      (node (ref "C12") (pin "2") (pinfunction "2_2") (pintype "passive"))
      (node (ref "C13") (pin "2") (pinfunction "2_2") (pintype "passive"))
      (node (ref "C14") (pin "2") (pinfunction "2_2") (pintype "passive"))
      (node (ref "C15") (pin "2") (pinfunction "2_2") (pintype "passive"))
      (node (ref "C16") (pin "2") (pinfunction "2_2") (pintype "passive"))
      (node (ref "C17") (pin "2") (pinfunction "2_2") (pintype "passive"))
      (node (ref "C18") (pin "2") (pinfunction "2_2") (pintype "passive"))
      (node (ref "C19") (pin "2") (pinfunction "2_2") (pintype "passive"))
      (node (ref "C2") (pin "2") (pinfunction "2_2") (pintype "passive"))
      (node (ref "C20") (pin "2") (pinfunction "2_2") (pintype "passive"))
      (node (ref "C21") (pin "2") (pinfunction "2_2") (pintype "passive"))
      (node (ref "C22") (pin "2") (pinfunction "2_2") (pintype "passive"))
      (node (ref "C23") (pin "2") (pinfunction "2_2") (pintype "passive"))
      (node (ref "C24") (pin "2") (pinfunction "2_2") (pintype "passive"))
      (node (ref "C25") (pin "2") (pinfunction "2_2") (pintype "passive"))
      (node (ref "C26") (pin "2") (pinfunction "2_2") (pintype "passive"))
      (node (ref "C27") (pin "2") (pinfunction "2_2") (pintype "passive"))
      (node (ref "C28") (pin "2") (pinfunction "2_2") (pintype "passive"))
      (node (ref "C29") (pin "2") (pinfunction "2_2") (pintype "passive"))
      (node (ref "C3") (pin "2") (pinfunction "2_2") (pintype "passive"))
      (node (ref "C30") (pin "2") (pinfunction "2_2") (pintype "passive"))
      (node (ref "C31") (pin "2") (pinfunction "2_2") (pintype "passive"))
      (node (ref "C33") (pin "2") (pinfunction "2_2") (pintype "passive"))
      (node (ref "C34") (pin "2") (pinfunction "2_2") (pintype "passive"))
      (node (ref "C35") (pin "2") (pinfunction "2_2") (pintype "passive"))
      (node (ref "C36") (pin "2") (pinfunction "2_2") (pintype "passive"))
      (node (ref "C37") (pin "2") (pinfunction "2_2") (pintype "passive"))
      (node (ref "C38") (pin "2") (pinfunction "2_2") (pintype "passive"))
      (node (ref "C39") (pin "2") (pinfunction "2_2") (pintype "passive"))
      (node (ref "C4") (pin "2") (pinfunction "2_2") (pintype "passive"))
      (node (ref "C40") (pin "2") (pinfunction "2_2") (pintype "passive"))
      (node (ref "C41") (pin "2") (pinfunction "2_2") (pintype "passive"))
      (node (ref "C42") (pin "2") (pinfunction "2_2") (pintype "passive"))
      (node (ref "C43") (pin "2") (pinfunction "2_2") (pintype "passive"))
      (node (ref "C44") (pin "2") (pinfunction "2_2") (pintype "passive"))
      (node (ref "C45") (pin "2") (pinfunction "2_2") (pintype "passive"))
      (node (ref "C46") (pin "2") (pinfunction "2_2") (pintype "passive"))
      (node (ref "C47") (pin "2") (pinfunction "2_2") (pintype "passive"))
      (node (ref "C48") (pin "2") (pinfunction "2_2") (pintype "passive"))
      (node (ref "C49") (pin "2") (pinfunction "2_2") (pintype "passive"))
      (node (ref "C5") (pin "2") (pinfunction "2_2") (pintype "passive"))
      (node (ref "C50") (pin "2") (pinfunction "2_2") (pintype "passive"))
      (node (ref "C51") (pin "-") (pinfunction "-_-") (pintype "passive"))
      (node (ref "C52") (pin "-") (pinfunction "-_-") (pintype "passive"))
      (node (ref "C53") (pin "-") (pinfunction "-_-") (pintype "passive"))
      (node (ref "C56") (pin "-") (pinfunction "-_-") (pintype "passive"))
      (node (ref "C57") (pin "2") (pinfunction "2_2") (pintype "passive"))
      (node (ref "C6") (pin "2") (pinfunction "2_2") (pintype "passive"))
      (node (ref "C7") (pin "2") (pinfunction "2_2") (pintype "passive"))
      (node (ref "C8") (pin "2") (pinfunction "2_2") (pintype "passive"))
      (node (ref "C9") (pin "2") (pinfunction "2_2") (pintype "passive"))
      (node (ref "DL1") (pin "2") (pinfunction "2_2") (pintype "passive"))
      (node (ref "E13") (pin "2") (pinfunction "R0(1)_2") (pintype "input"))
      (node (ref "E13") (pin "3") (pinfunction "R0(2)_3") (pintype "input"))
      (node (ref "E14") (pin "2") (pinfunction "R0(1)_2") (pintype "input"))
      (node (ref "E14") (pin "3") (pinfunction "R0(2)_3") (pintype "input"))
      (node (ref "E16") (pin "12") (pinfunction "D_12") (pintype "input"))
      (node (ref "E17") (pin "2") (pinfunction "R0(1)_2") (pintype "input"))
      (node (ref "E17") (pin "3") (pinfunction "R0(2)_3") (pintype "input"))
      (node (ref "E18") (pin "1") (pinfunction "CKB_1") (pintype "input"))
      (node (ref "E18") (pin "2") (pinfunction "R0(1)_2") (pintype "input"))
      (node (ref "E18") (pin "3") (pinfunction "R0(2)_3") (pintype "input"))
      (node (ref "E3") (pin "12") (pinfunction "D_12") (pintype "input"))
      (node (ref "E34") (pin "10") (pinfunction "I1_10") (pintype "input"))
      (node (ref "E34") (pin "11") (pinfunction "I0_11") (pintype "input"))
      (node (ref "E36") (pin "10") (pinfunction "I1_10") (pintype "input"))
      (node (ref "E36") (pin "11") (pinfunction "I0_11") (pintype "input"))
      (node (ref "E7") (pin "12") (pinfunction "D_12") (pintype "input"))
      (node (ref "E7") (pin "2") (pinfunction "D_2") (pintype "input"))
      (node (ref "E9") (pin "2") (pinfunction "R0(1)_2") (pintype "input"))
      (node (ref "E9") (pin "3") (pinfunction "R0(2)_3") (pintype "input"))
      (node (ref "IC1") (pin "4") (pinfunction "G2A_4") (pintype "input"))
      (node (ref "IC1") (pin "5") (pinfunction "G2B_5") (pintype "input"))
      (node (ref "IC2") (pin "5") (pinfunction "G2B_5") (pintype "input"))
      (node (ref "IC3") (pin "7") (pinfunction "G_7") (pintype "input"))
      (node (ref "IC4") (pin "7") (pinfunction "G_7") (pintype "input"))
      (node (ref "IC5") (pin "5") (pinfunction "G2B_5") (pintype "input"))
      (node (ref "IC6") (pin "5") (pinfunction "G2B_5") (pintype "input"))
      (node (ref "IC7") (pin "5") (pinfunction "G2B_5") (pintype "input"))
      (node (ref "IC8") (pin "7") (pinfunction "G_7") (pintype "input"))
      (node (ref "OSC") (pin "4") (pinfunction "GND_4") (pintype "power_in"))
      (node (ref "OSC1") (pin "7") (pinfunction "GND_7") (pintype "power_in"))
      (node (ref "R2") (pin "1") (pinfunction "1_1") (pintype "passive"))
      (node (ref "R20") (pin "2") (pinfunction "2_2") (pintype "passive"))
      (node (ref "SW1") (pin "1") (pinfunction "1_1") (pintype "passive"))
      (node (ref "SW1") (pin "2") (pinfunction "2_2") (pintype "passive"))
      (node (ref "SW1") (pin "3") (pinfunction "3_3") (pintype "passive"))
      (node (ref "SW1") (pin "4") (pinfunction "4_4") (pintype "passive"))
      (node (ref "SW1") (pin "5") (pinfunction "5_5") (pintype "passive"))
      (node (ref "SW1") (pin "6") (pinfunction "6_6") (pintype "passive"))
      (node (ref "U$2") (pin "AC2") (pinfunction "1_AC2") (pintype "bidirectional"))
      (node (ref "U$2") (pin "AF1") (pinfunction "1_AF1") (pintype "bidirectional"))
      (node (ref "U$2") (pin "AF2") (pinfunction "1_AF2") (pintype "bidirectional"))
      (node (ref "U$2") (pin "AN1") (pinfunction "1_AN1") (pintype "bidirectional"))
      (node (ref "U$2") (pin "AN2") (pinfunction "1_AN2") (pintype "bidirectional"))
      (node (ref "U$2") (pin "AT1") (pinfunction "1_AT1") (pintype "bidirectional"))
      (node (ref "U$2") (pin "AT2") (pinfunction "1_AT2") (pintype "bidirectional"))
      (node (ref "U$2") (pin "BC1") (pinfunction "1_BC1") (pintype "bidirectional"))
      (node (ref "U$2") (pin "BC2") (pinfunction "1_BC2") (pintype "bidirectional"))
      (node (ref "U$2") (pin "BF1") (pinfunction "1_BF1") (pintype "bidirectional"))
      (node (ref "U$2") (pin "BF2") (pinfunction "1_BF2") (pintype "bidirectional"))
      (node (ref "U$2") (pin "BN1") (pinfunction "1_BN1") (pintype "bidirectional"))
      (node (ref "U$2") (pin "BN2") (pinfunction "1_BN2") (pintype "bidirectional"))
      (node (ref "U$2") (pin "BT1") (pinfunction "1_BT1") (pintype "bidirectional"))
      (node (ref "U$2") (pin "BT2") (pinfunction "1_BT2") (pintype "bidirectional"))
      (node (ref "U$2") (pin "CC1") (pinfunction "1_CC1") (pintype "bidirectional"))
      (node (ref "U$2") (pin "CC2") (pinfunction "1_CC2") (pintype "bidirectional"))
      (node (ref "U$2") (pin "CF1") (pinfunction "1_CF1") (pintype "bidirectional"))
      (node (ref "U$2") (pin "CF2") (pinfunction "1_CF2") (pintype "bidirectional"))
      (node (ref "U$2") (pin "CN1") (pinfunction "1_CN1") (pintype "bidirectional"))
      (node (ref "U$2") (pin "CN2") (pinfunction "1_CN2") (pintype "bidirectional"))
      (node (ref "U$2") (pin "CT1") (pinfunction "1_CT1") (pintype "bidirectional"))
      (node (ref "U$2") (pin "CT2") (pinfunction "1_CT2") (pintype "bidirectional"))
      (node (ref "U$2") (pin "DC1") (pinfunction "1_DC1") (pintype "bidirectional"))
      (node (ref "U$2") (pin "DC2") (pinfunction "1_DC2") (pintype "bidirectional"))
      (node (ref "U$2") (pin "DF1") (pinfunction "1_DF1") (pintype "bidirectional"))
      (node (ref "U$2") (pin "DF2") (pinfunction "1_DF2") (pintype "bidirectional"))
      (node (ref "U$2") (pin "DN1") (pinfunction "1_DN1") (pintype "bidirectional"))
      (node (ref "U$2") (pin "DN2") (pinfunction "1_DN2") (pintype "bidirectional"))
      (node (ref "U$2") (pin "DT1") (pinfunction "1_DT1") (pintype "bidirectional"))
      (node (ref "U$2") (pin "DT2") (pinfunction "1_DT2") (pintype "bidirectional"))
      (node (ref "USB") (pin "5") (pinfunction "5_5") (pintype "passive"))
      (node (ref "USB") (pin "G1") (pinfunction "G1_G1") (pintype "passive"))
      (node (ref "USB") (pin "G2") (pinfunction "G2_G2") (pintype "passive"))
    )
    (net (code "46") (name "INITIALIZE") (class "Default")
      (node (ref "E36") (pin "9") (pinfunction "I0_9") (pintype "input"))
      (node (ref "U$2") (pin "CR1") (pinfunction "1_CR1") (pintype "bidirectional"))
    )
    (net (code "47") (name "INIT_L") (class "Default")
      (node (ref "E20") (pin "4") (pinfunction "PRE_4") (pintype "input"))
      (node (ref "E28") (pin "1") (pinfunction "R_1") (pintype "input"))
      (node (ref "E31") (pin "1") (pinfunction "R_1") (pintype "input"))
      (node (ref "E35") (pin "11") (pinfunction "O_11") (pintype "output"))
      (node (ref "E35") (pin "5") (pinfunction "I1_5") (pintype "input"))
      (node (ref "E38") (pin "13") (pinfunction "CLR_13") (pintype "input"))
      (node (ref "E41") (pin "1") (pinfunction "I0_1") (pintype "input"))
    )
    (net (code "48") (name "INTERNAL_IO_L") (class "Default")
      (node (ref "E37") (pin "1") (pinfunction "O_1") (pintype "open_collector"))
      (node (ref "E37") (pin "4") (pinfunction "O_4") (pintype "open_collector"))
      (node (ref "U$2") (pin "CL1") (pinfunction "1_CL1") (pintype "bidirectional"))
    )
    (net (code "49") (name "INT_ENAB") (class "Default")
      (node (ref "E37") (pin "12") (pinfunction "I1_12") (pintype "input"))
      (node (ref "E38") (pin "8") (pinfunction "~{Q}_8") (pintype "output"))
      (node (ref "U$2") (pin "CB1") (pinfunction "1_CB1") (pintype "bidirectional"))
    )
    (net (code "50") (name "INT_RQST_L") (class "Default")
      (node (ref "E37") (pin "13") (pinfunction "O_13") (pintype "open_collector"))
      (node (ref "U$2") (pin "CP1") (pinfunction "1_CP1") (pintype "bidirectional"))
    )
    (net (code "51") (name "IOT0X_L") (class "Default")
      (node (ref "IC1") (pin "7") (pinfunction "Y7_7") (pintype "output"))
      (node (ref "IC5") (pin "4") (pinfunction "G2A_4") (pintype "input"))
    )
    (net (code "52") (name "IOT1X_L") (class "Default")
      (node (ref "IC1") (pin "9") (pinfunction "Y6_9") (pintype "output"))
      (node (ref "IC6") (pin "4") (pinfunction "G2A_4") (pintype "input"))
    )
    (net (code "53") (name "IOT3X_L") (class "Default")
      (node (ref "IC1") (pin "11") (pinfunction "Y4_11") (pintype "output"))
      (node (ref "IC7") (pin "4") (pinfunction "G2A_4") (pintype "input"))
    )
    (net (code "54") (name "IOT03_L") (class "Default")
      (node (ref "IC4") (pin "3") (pinfunction "D1_3") (pintype "input"))
      (node (ref "IC5") (pin "11") (pinfunction "Y4_11") (pintype "output"))
    )
    (net (code "55") (name "IOT4X_L") (class "Default")
      (node (ref "IC1") (pin "12") (pinfunction "Y3_12") (pintype "output"))
      (node (ref "IC2") (pin "4") (pinfunction "G2A_4") (pintype "input"))
    )
    (net (code "56") (name "IOT04_L") (class "Default")
      (node (ref "IC3") (pin "3") (pinfunction "D1_3") (pintype "input"))
      (node (ref "IC5") (pin "12") (pinfunction "Y3_12") (pintype "output"))
    )
    (net (code "57") (name "IOT11_L") (class "Default")
      (node (ref "IC4") (pin "12") (pinfunction "D7_12") (pintype "input"))
      (node (ref "IC6") (pin "9") (pinfunction "Y6_9") (pintype "output"))
    )
    (net (code "58") (name "IOT12_L") (class "Default")
      (node (ref "IC3") (pin "12") (pinfunction "D7_12") (pintype "input"))
      (node (ref "IC6") (pin "10") (pinfunction "Y5_10") (pintype "output"))
    )
    (net (code "59") (name "IOT34_L") (class "Default")
      (node (ref "IC4") (pin "13") (pinfunction "D6_13") (pintype "input"))
      (node (ref "IC7") (pin "12") (pinfunction "Y3_12") (pintype "output"))
    )
    (net (code "60") (name "IOT35_L") (class "Default")
      (node (ref "IC3") (pin "13") (pinfunction "D6_13") (pintype "input"))
      (node (ref "IC7") (pin "13") (pinfunction "Y2_13") (pintype "output"))
    )
    (net (code "61") (name "IOT40_L") (class "Default")
      (node (ref "IC2") (pin "7") (pinfunction "Y7_7") (pintype "output"))
      (node (ref "IC4") (pin "2") (pinfunction "D2_2") (pintype "input"))
    )
    (net (code "62") (name "IOT41_L") (class "Default")
      (node (ref "IC2") (pin "9") (pinfunction "Y6_9") (pintype "output"))
      (node (ref "IC3") (pin "2") (pinfunction "D2_2") (pintype "input"))
    )
    (net (code "63") (name "IOT42_L") (class "Default")
      (node (ref "IC2") (pin "10") (pinfunction "Y5_10") (pintype "output"))
      (node (ref "IC4") (pin "1") (pinfunction "D3_1") (pintype "input"))
    )
    (net (code "64") (name "IOT43_L") (class "Default")
      (node (ref "IC2") (pin "11") (pinfunction "Y4_11") (pintype "output"))
      (node (ref "IC3") (pin "1") (pinfunction "D3_1") (pintype "input"))
    )
    (net (code "65") (name "IOT44_L") (class "Default")
      (node (ref "IC2") (pin "12") (pinfunction "Y3_12") (pintype "output"))
      (node (ref "IC4") (pin "15") (pinfunction "D4_15") (pintype "input"))
    )
    (net (code "66") (name "IOT45_L") (class "Default")
      (node (ref "IC2") (pin "13") (pinfunction "Y2_13") (pintype "output"))
      (node (ref "IC3") (pin "15") (pinfunction "D4_15") (pintype "input"))
    )
    (net (code "67") (name "IOT46_L") (class "Default")
      (node (ref "IC2") (pin "14") (pinfunction "Y1_14") (pintype "output"))
      (node (ref "IC4") (pin "14") (pinfunction "D5_14") (pintype "input"))
    )
    (net (code "68") (name "IOT47_L") (class "Default")
      (node (ref "IC2") (pin "15") (pinfunction "Y0_15") (pintype "output"))
      (node (ref "IC3") (pin "14") (pinfunction "D5_14") (pintype "input"))
    )
    (net (code "69") (name "IO_PAUSE_L") (class "Default")
      (node (ref "E34") (pin "12") (pinfunction "I1_12") (pintype "input"))
      (node (ref "U$2") (pin "CD1") (pinfunction "1_CD1") (pintype "bidirectional"))
    )
    (net (code "70") (name "IS110") (class "Default")
      (node (ref "E23") (pin "7") (pinfunction "I1_7") (pintype "input"))
      (node (ref "IC12") (pin "12") (pinfunction "O_12") (pintype "output"))
      (node (ref "IC12") (pin "3") (pinfunction "I0_3") (pintype "input"))
      (node (ref "IC12") (pin "4") (pinfunction "I1_4") (pintype "input"))
      (node (ref "IC12") (pin "5") (pinfunction "I2_5") (pintype "input"))
    )
    (net (code "71") (name "KSKP") (class "Default")
      (node (ref "E45") (pin "5") (pinfunction "I0_5") (pintype "input"))
      (node (ref "E47") (pin "13") (pinfunction "O_13") (pintype "output"))
    )
    (net (code "72") (name "LAST_UNIT") (class "Default")
      (node (ref "E39") (pin "13") (pinfunction "I3_13") (pintype "input"))
      (node (ref "E8") (pin "5") (pinfunction "Q_5") (pintype "output"))
    )
    (net (code "73") (name "MD03_L") (class "Default")
      (node (ref "IC1") (pin "3") (pinfunction "C_3") (pintype "input"))
      (node (ref "U$2") (pin "AP1") (pinfunction "1_AP1") (pintype "bidirectional"))
    )
    (net (code "74") (name "MD04_L") (class "Default")
      (node (ref "IC1") (pin "2") (pinfunction "B_2") (pintype "input"))
      (node (ref "U$2") (pin "BK1") (pinfunction "1_BK1") (pintype "bidirectional"))
    )
    (net (code "75") (name "MD05_L") (class "Default")
      (node (ref "IC1") (pin "1") (pinfunction "A_1") (pintype "input"))
      (node (ref "U$2") (pin "BL1") (pinfunction "1_BL1") (pintype "bidirectional"))
    )
    (net (code "76") (name "MD06_L") (class "Default")
      (node (ref "IC2") (pin "3") (pinfunction "C_3") (pintype "input"))
      (node (ref "IC5") (pin "3") (pinfunction "C_3") (pintype "input"))
      (node (ref "IC6") (pin "3") (pinfunction "C_3") (pintype "input"))
      (node (ref "IC7") (pin "3") (pinfunction "C_3") (pintype "input"))
      (node (ref "U$2") (pin "BM1") (pinfunction "1_BM1") (pintype "bidirectional"))
    )
    (net (code "77") (name "MD07_L") (class "Default")
      (node (ref "IC2") (pin "2") (pinfunction "B_2") (pintype "input"))
      (node (ref "IC5") (pin "2") (pinfunction "B_2") (pintype "input"))
      (node (ref "IC6") (pin "2") (pinfunction "B_2") (pintype "input"))
      (node (ref "IC7") (pin "2") (pinfunction "B_2") (pintype "input"))
      (node (ref "U$2") (pin "BP1") (pinfunction "1_BP1") (pintype "bidirectional"))
    )
    (net (code "78") (name "MD08_L") (class "Default")
      (node (ref "IC2") (pin "1") (pinfunction "A_1") (pintype "input"))
      (node (ref "IC5") (pin "1") (pinfunction "A_1") (pintype "input"))
      (node (ref "IC6") (pin "1") (pinfunction "A_1") (pintype "input"))
      (node (ref "IC7") (pin "1") (pinfunction "A_1") (pintype "input"))
      (node (ref "U$2") (pin "DK1") (pinfunction "1_DK1") (pintype "bidirectional"))
    )
    (net (code "79") (name "MD09_L") (class "Default")
      (node (ref "E46") (pin "7") (pinfunction "I1_7") (pintype "input"))
      (node (ref "U$2") (pin "DL1") (pinfunction "1_DL1") (pintype "bidirectional"))
    )
    (net (code "80") (name "MD10_L") (class "Default")
      (node (ref "E46") (pin "4") (pinfunction "I0_4") (pintype "input"))
      (node (ref "U$2") (pin "DM1") (pinfunction "1_DM1") (pintype "bidirectional"))
    )
    (net (code "81") (name "MD11_L") (class "Default")
      (node (ref "E46") (pin "9") (pinfunction "I0_9") (pintype "input"))
      (node (ref "U$2") (pin "DP1") (pinfunction "1_DP1") (pintype "bidirectional"))
    )
    (net (code "82") (name "NOT110") (class "Default")
      (node (ref "E23") (pin "9") (pinfunction "I0_9") (pintype "input"))
      (node (ref "IC12") (pin "6") (pinfunction "O_6") (pintype "output"))
    )
    (net (code "83") (name "Net-(E1A-I0)") (class "Default")
      (node (ref "E1") (pin "4") (pinfunction "I0_4") (pintype "input"))
      (node (ref "E1") (pin "5") (pinfunction "I1_5") (pintype "input"))
      (node (ref "IC8") (pin "6") (pinfunction "W_6") (pintype "output"))
    )
    (net (code "84") (name "Net-(E1D-O)") (class "Default")
      (node (ref "E1") (pin "13") (pinfunction "O_13") (pintype "output"))
      (node (ref "E48") (pin "11") (pinfunction "CLK_11") (pintype "input"))
    )
    (net (code "85") (name "Net-(E2B-I1)") (class "Default")
      (node (ref "E2") (pin "6") (pinfunction "I1_6") (pintype "input"))
      (node (ref "E6") (pin "9") (pinfunction "Q2_9") (pintype "output"))
    )
    (net (code "86") (name "Net-(E2C-I0)") (class "Default")
      (node (ref "E2") (pin "8") (pinfunction "I0_8") (pintype "input"))
      (node (ref "E6") (pin "7") (pinfunction "Q1_7") (pintype "output"))
    )
    (net (code "87") (name "Net-(E5A-CKB)") (class "Default")
      (node (ref "E5") (pin "1") (pinfunction "CKB_1") (pintype "input"))
      (node (ref "E5") (pin "12") (pinfunction "QA_12") (pintype "output"))
      (node (ref "IC9") (pin "1") (pinfunction "I0_1") (pintype "input"))
    )
    (net (code "88") (name "Net-(E5A-QB)") (class "Default")
      (node (ref "E5") (pin "9") (pinfunction "QB_9") (pintype "output"))
      (node (ref "IC9") (pin "2") (pinfunction "I1_2") (pintype "input"))
    )
    (net (code "89") (name "Net-(E8B-D)") (class "Default")
      (node (ref "E8") (pin "12") (pinfunction "D_12") (pintype "input"))
      (node (ref "E8") (pin "8") (pinfunction "~{Q}_8") (pintype "output"))
    )
    (net (code "90") (name "Net-(E10A-C)") (class "Default")
      (node (ref "E10") (pin "6") (pinfunction "C_6") (pintype "input"))
      (node (ref "E11") (pin "4") (pinfunction "O_4") (pintype "output"))
      (node (ref "E6") (pin "6") (pinfunction "C_6") (pintype "input"))
    )
    (net (code "91") (name "Net-(E10A-D)") (class "Default")
      (node (ref "E10") (pin "4") (pinfunction "D_4") (pintype "input"))
      (node (ref "E2") (pin "2") (pinfunction "I0_2") (pintype "input"))
      (node (ref "E6") (pin "11") (pinfunction "Q3_11") (pintype "output"))
    )
    (net (code "92") (name "Net-(E10A-Q0)") (class "Default")
      (node (ref "E10") (pin "5") (pinfunction "Q0_5") (pintype "output"))
      (node (ref "E15") (pin "12") (pinfunction "I1_12") (pintype "input"))
    )
    (net (code "93") (name "Net-(E10A-Q1)") (class "Default")
      (node (ref "E10") (pin "7") (pinfunction "Q1_7") (pintype "output"))
      (node (ref "E15") (pin "8") (pinfunction "I0_8") (pintype "input"))
    )
    (net (code "94") (name "Net-(E10A-Q2)") (class "Default")
      (node (ref "E10") (pin "9") (pinfunction "Q2_9") (pintype "output"))
      (node (ref "E15") (pin "6") (pinfunction "I1_6") (pintype "input"))
    )
    (net (code "95") (name "Net-(E10A-Q3)") (class "Default")
      (node (ref "E10") (pin "11") (pinfunction "Q3_11") (pintype "output"))
      (node (ref "E15") (pin "2") (pinfunction "I0_2") (pintype "input"))
    )
    (net (code "96") (name "Net-(E11A-O)") (class "Default")
      (node (ref "E11") (pin "1") (pinfunction "O_1") (pintype "output"))
      (node (ref "E39") (pin "9") (pinfunction "I2_9") (pintype "input"))
    )
    (net (code "97") (name "Net-(E11B-I1)") (class "Default")
      (node (ref "E11") (pin "10") (pinfunction "O_10") (pintype "output"))
      (node (ref "E11") (pin "6") (pinfunction "I1_6") (pintype "input"))
    )
    (net (code "98") (name "Net-(E11D-O)") (class "Default")
      (node (ref "E11") (pin "13") (pinfunction "O_13") (pintype "output"))
      (node (ref "E3") (pin "11") (pinfunction "CLK_11") (pintype "input"))
    )
    (net (code "99") (name "Net-(E12B-O)") (class "Default")
      (node (ref "E12") (pin "6") (pinfunction "O_6") (pintype "output"))
      (node (ref "E8") (pin "1") (pinfunction "CLR_1") (pintype "input"))
    )
    (net (code "100") (name "Net-(E12C-O)") (class "Default")
      (node (ref "E12") (pin "8") (pinfunction "O_8") (pintype "output"))
      (node (ref "E3") (pin "2") (pinfunction "D_2") (pintype "input"))
    )
    (net (code "101") (name "Net-(E16A-D)") (class "Default")
      (node (ref "E16") (pin "2") (pinfunction "D_2") (pintype "input"))
      (node (ref "E35") (pin "8") (pinfunction "O_8") (pintype "output"))
    )
    (net (code "102") (name "Net-(E19A-I1)") (class "Default")
      (node (ref "E19") (pin "2") (pinfunction "I1_2") (pintype "input"))
      (node (ref "E21") (pin "10") (pinfunction "O_10") (pintype "output"))
    )
    (net (code "103") (name "Net-(E19B-I0)") (class "Default")
      (node (ref "E19") (pin "11") (pinfunction "I2_11") (pintype "input"))
      (node (ref "E19") (pin "3") (pinfunction "I0_3") (pintype "input"))
      (node (ref "E24") (pin "8") (pinfunction "O_8") (pintype "output"))
    )
    (net (code "104") (name "Net-(E19B-I2)") (class "Default")
      (node (ref "E19") (pin "10") (pinfunction "I1_10") (pintype "input"))
      (node (ref "E19") (pin "5") (pinfunction "I2_5") (pintype "input"))
      (node (ref "E19") (pin "9") (pinfunction "I0_9") (pintype "input"))
      (node (ref "E24") (pin "6") (pinfunction "O_6") (pintype "output"))
    )
    (net (code "105") (name "Net-(E20A-D)") (class "Default")
      (node (ref "E20") (pin "2") (pinfunction "D_2") (pintype "input"))
      (node (ref "E25") (pin "8") (pinfunction "O_8") (pintype "output"))
    )
    (net (code "106") (name "Net-(E21A-I)") (class "Default")
      (node (ref "E21") (pin "1") (pinfunction "I_1") (pintype "input"))
      (node (ref "E39") (pin "8") (pinfunction "O_8") (pintype "output"))
    )
    (net (code "107") (name "Net-(E21A-O)") (class "Default")
      (node (ref "E21") (pin "2") (pinfunction "O_2") (pintype "output"))
      (node (ref "E7") (pin "3") (pinfunction "CLK_3") (pintype "input"))
    )
    (net (code "108") (name "Net-(E21B-O)") (class "Default")
      (node (ref "E21") (pin "4") (pinfunction "O_4") (pintype "output"))
      (node (ref "E29") (pin "11") (pinfunction "CLK_11") (pintype "input"))
    )
    (net (code "109") (name "Net-(E21C-O)") (class "Default")
      (node (ref "E21") (pin "6") (pinfunction "O_6") (pintype "output"))
      (node (ref "E26") (pin "6") (pinfunction "C_6") (pintype "input"))
    )
    (net (code "110") (name "Net-(E21D-O)") (class "Default")
      (node (ref "E21") (pin "8") (pinfunction "O_8") (pintype "output"))
      (node (ref "E6") (pin "4") (pinfunction "D_4") (pintype "input"))
    )
    (net (code "111") (name "Net-(E23B-O)") (class "Default")
      (node (ref "E23") (pin "11") (pinfunction "I0_11") (pintype "input"))
      (node (ref "E23") (pin "2") (pinfunction "O_2") (pintype "output"))
    )
    (net (code "112") (name "Net-(E23C-O)") (class "Default")
      (node (ref "E23") (pin "12") (pinfunction "I1_12") (pintype "input"))
      (node (ref "E23") (pin "14") (pinfunction "O_14") (pintype "output"))
    )
    (net (code "113") (name "Net-(E24A-I0)") (class "Default")
      (node (ref "E24") (pin "1") (pinfunction "I0_1") (pintype "input"))
      (node (ref "E28") (pin "9") (pinfunction "Q2_9") (pintype "output"))
    )
    (net (code "114") (name "Net-(E24A-I2)") (class "Default")
      (node (ref "E24") (pin "4") (pinfunction "I2_4") (pintype "input"))
      (node (ref "E28") (pin "5") (pinfunction "Q0_5") (pintype "output"))
    )
    (net (code "115") (name "Net-(E24A-I3)") (class "Default")
      (node (ref "E24") (pin "5") (pinfunction "I3_5") (pintype "input"))
      (node (ref "E28") (pin "7") (pinfunction "Q1_7") (pintype "output"))
    )
    (net (code "116") (name "Net-(E24B-I0)") (class "Default")
      (node (ref "E24") (pin "9") (pinfunction "I0_9") (pintype "input"))
      (node (ref "E31") (pin "5") (pinfunction "Q0_5") (pintype "output"))
    )
    (net (code "117") (name "Net-(E24B-I1)") (class "Default")
      (node (ref "E24") (pin "10") (pinfunction "I1_10") (pintype "input"))
      (node (ref "E31") (pin "7") (pinfunction "Q1_7") (pintype "output"))
    )
    (net (code "118") (name "Net-(E24B-I2)") (class "Default")
      (node (ref "E24") (pin "12") (pinfunction "I2_12") (pintype "input"))
      (node (ref "E31") (pin "9") (pinfunction "Q2_9") (pintype "output"))
    )
    (net (code "119") (name "Net-(E24B-I3)") (class "Default")
      (node (ref "E24") (pin "13") (pinfunction "I3_13") (pintype "input"))
      (node (ref "E28") (pin "11") (pinfunction "Q3_11") (pintype "output"))
      (node (ref "E31") (pin "4") (pinfunction "D_4") (pintype "input"))
    )
    (net (code "120") (name "Net-(E25B-I4)") (class "Default")
      (node (ref "DL1") (pin "3") (pinfunction "3_3") (pintype "passive"))
      (node (ref "E25") (pin "5") (pinfunction "I4_5") (pintype "input"))
      (node (ref "R20") (pin "1") (pinfunction "1_1") (pintype "passive"))
    )
    (net (code "121") (name "Net-(E27A-O)") (class "Default")
      (node (ref "E27") (pin "3") (pinfunction "O_3") (pintype "output"))
      (node (ref "E28") (pin "2") (pinfunction "I1_2") (pintype "input"))
    )
    (net (code "122") (name "Net-(E27B-O)") (class "Default")
      (node (ref "E27") (pin "2") (pinfunction "O_2") (pintype "output"))
      (node (ref "E28") (pin "3") (pinfunction "I0_3") (pintype "input"))
    )
    (net (code "123") (name "Net-(E27C-O)") (class "Default")
      (node (ref "E27") (pin "14") (pinfunction "O_14") (pintype "output"))
      (node (ref "E28") (pin "14") (pinfunction "I3_14") (pintype "input"))
    )
    (net (code "124") (name "Net-(E27D-O)") (class "Default")
      (node (ref "E27") (pin "13") (pinfunction "O_13") (pintype "output"))
      (node (ref "E28") (pin "15") (pinfunction "I2_15") (pintype "input"))
    )
    (net (code "125") (name "Net-(E30A-O)") (class "Default")
      (node (ref "E30") (pin "3") (pinfunction "O_3") (pintype "output"))
      (node (ref "E31") (pin "2") (pinfunction "I1_2") (pintype "input"))
    )
    (net (code "126") (name "Net-(E30B-O)") (class "Default")
      (node (ref "E30") (pin "2") (pinfunction "O_2") (pintype "output"))
      (node (ref "E31") (pin "3") (pinfunction "I0_3") (pintype "input"))
    )
    (net (code "127") (name "Net-(E30C-O)") (class "Default")
      (node (ref "E30") (pin "14") (pinfunction "O_14") (pintype "output"))
      (node (ref "E31") (pin "14") (pinfunction "I3_14") (pintype "input"))
    )
    (net (code "128") (name "Net-(E30D-O)") (class "Default")
      (node (ref "E30") (pin "13") (pinfunction "O_13") (pintype "output"))
      (node (ref "E31") (pin "15") (pinfunction "I2_15") (pintype "input"))
    )
    (net (code "129") (name "Net-(E34B-O)") (class "Default")
      (node (ref "E34") (pin "2") (pinfunction "O_2") (pintype "output"))
      (node (ref "E38") (pin "12") (pinfunction "D_12") (pintype "input"))
    )
    (net (code "130") (name "Net-(E35B-O)") (class "Default")
      (node (ref "E35") (pin "6") (pinfunction "O_6") (pintype "output"))
      (node (ref "E47") (pin "2") (pinfunction "I0_2") (pintype "input"))
    )
    (net (code "131") (name "Net-(E35D-I0)") (class "Default")
      (node (ref "E35") (pin "12") (pinfunction "I0_12") (pintype "input"))
      (node (ref "E35") (pin "13") (pinfunction "I1_13") (pintype "input"))
      (node (ref "E36") (pin "14") (pinfunction "O_14") (pintype "output"))
      (node (ref "E46") (pin "11") (pinfunction "I0_11") (pintype "input"))
      (node (ref "E46") (pin "12") (pinfunction "I1_12") (pintype "input"))
    )
    (net (code "132") (name "Net-(E36D-O)") (class "Default")
      (node (ref "E36") (pin "13") (pinfunction "O_13") (pintype "output"))
      (node (ref "E7") (pin "1") (pinfunction "CLR_1") (pintype "input"))
    )
    (net (code "133") (name "Net-(E37C-I0)") (class "Default")
      (node (ref "E37") (pin "8") (pinfunction "I0_8") (pintype "input"))
      (node (ref "E37") (pin "9") (pinfunction "I1_9") (pintype "input"))
      (node (ref "E42") (pin "8") (pinfunction "O_8") (pintype "output"))
    )
    (net (code "134") (name "Net-(E38A-PRE)") (class "Default")
      (node (ref "E38") (pin "4") (pinfunction "PRE_4") (pintype "input"))
      (node (ref "E42") (pin "6") (pinfunction "O_6") (pintype "output"))
    )
    (net (code "135") (name "Net-(E39B-I1)") (class "Default")
      (node (ref "E39") (pin "2") (pinfunction "I1_2") (pintype "input"))
      (node (ref "E45") (pin "10") (pinfunction "O_10") (pintype "output"))
    )
    (net (code "136") (name "Net-(E39B-O)") (class "Default")
      (node (ref "E39") (pin "6") (pinfunction "O_6") (pintype "output"))
      (node (ref "E42") (pin "9") (pinfunction "I_9") (pintype "input"))
    )
    (net (code "137") (name "Net-(E40A-A)") (class "Default")
      (node (ref "E40") (pin "15") (pinfunction "A_15") (pintype "input"))
      (node (ref "E43") (pin "15") (pinfunction "A_15") (pintype "input"))
      (node (ref "E46") (pin "14") (pinfunction "O_14") (pintype "output"))
    )
    (net (code "138") (name "Net-(E40A-B)") (class "Default")
      (node (ref "E40") (pin "14") (pinfunction "B_14") (pintype "input"))
      (node (ref "E43") (pin "14") (pinfunction "B_14") (pintype "input"))
      (node (ref "E46") (pin "3") (pinfunction "O_3") (pintype "output"))
    )
    (net (code "139") (name "Net-(E40A-C)") (class "Default")
      (node (ref "E40") (pin "1") (pinfunction "C_1") (pintype "input"))
      (node (ref "E43") (pin "1") (pinfunction "C_1") (pintype "input"))
      (node (ref "E46") (pin "2") (pinfunction "O_2") (pintype "output"))
    )
    (net (code "140") (name "Net-(E41A-O)") (class "Default")
      (node (ref "E41") (pin "3") (pinfunction "O_3") (pintype "output"))
      (node (ref "E42") (pin "5") (pinfunction "I_5") (pintype "input"))
    )
    (net (code "141") (name "Net-(E42E-I)") (class "Default")
      (node (ref "E42") (pin "11") (pinfunction "I_11") (pintype "input"))
      (node (ref "E45") (pin "4") (pinfunction "O_4") (pintype "output"))
    )
    (net (code "142") (name "Net-(E47A-O)") (class "Default")
      (node (ref "E47") (pin "1") (pinfunction "O_1") (pintype "output"))
      (node (ref "E48") (pin "1") (pinfunction "CLR_1") (pintype "input"))
    )
    (net (code "143") (name "PAUSE") (class "Default")
      (node (ref "E21") (pin "12") (pinfunction "O_12") (pintype "output"))
      (node (ref "IC1") (pin "6") (pinfunction "G1_6") (pintype "input"))
      (node (ref "IC2") (pin "6") (pinfunction "G1_6") (pintype "input"))
      (node (ref "IC5") (pin "6") (pinfunction "G1_6") (pintype "input"))
      (node (ref "IC6") (pin "6") (pinfunction "G1_6") (pintype "input"))
      (node (ref "IC7") (pin "6") (pinfunction "G1_6") (pintype "input"))
    )
    (net (code "144") (name "POWER_OK") (class "Default")
      (node (ref "E36") (pin "12") (pinfunction "I1_12") (pintype "input"))
      (node (ref "U$2") (pin "BV2") (pinfunction "1_BV2") (pintype "bidirectional"))
    )
    (net (code "145") (name "RX7") (class "Default")
      (node (ref "E1") (pin "11") (pinfunction "I0_11") (pintype "input"))
      (node (ref "E1") (pin "12") (pinfunction "I1_12") (pintype "input"))
      (node (ref "E2") (pin "12") (pinfunction "I1_12") (pintype "input"))
      (node (ref "E6") (pin "5") (pinfunction "Q0_5") (pintype "output"))
      (node (ref "R24") (pin "1") (pinfunction "1_1") (pintype "passive"))
    )
    (net (code "146") (name "RX_ACTIVE") (class "Default")
      (node (ref "E12") (pin "1") (pinfunction "I0_1") (pintype "input"))
      (node (ref "E7") (pin "11") (pinfunction "CLK_11") (pintype "input"))
      (node (ref "E7") (pin "5") (pinfunction "Q_5") (pintype "output"))
    )
    (net (code "147") (name "RX_BOT") (class "Default")
      (node (ref "E10") (pin "12") (pinfunction "Q4_12") (pintype "output"))
      (node (ref "E48") (pin "2") (pinfunction "D_2") (pintype "input"))
      (node (ref "E8") (pin "2") (pinfunction "D_2") (pintype "input"))
    )
    (net (code "148") (name "RX_DIV") (class "Default")
      (node (ref "E12") (pin "9") (pinfunction "I0_9") (pintype "input"))
      (node (ref "E3") (pin "5") (pinfunction "Q_5") (pintype "output"))
    )
    (net (code "149") (name "RX_DIV8") (class "Default")
      (node (ref "E12") (pin "2") (pinfunction "I1_2") (pintype "input"))
      (node (ref "E12") (pin "5") (pinfunction "I1_5") (pintype "input"))
      (node (ref "E8") (pin "9") (pinfunction "Q_9") (pintype "output"))
    )
    (net (code "150") (name "RX_LAST") (class "Default")
      (node (ref "E36") (pin "3") (pinfunction "O_3") (pintype "output"))
      (node (ref "E4") (pin "1") (pinfunction "CLR_1") (pintype "input"))
      (node (ref "E4") (pin "13") (pinfunction "CLR_13") (pintype "input"))
      (node (ref "E8") (pin "13") (pinfunction "CLR_13") (pintype "input"))
    )
    (net (code "151") (name "RX_RATE") (class "Default")
      (node (ref "E19") (pin "13") (pinfunction "I2_13") (pintype "input"))
      (node (ref "E3") (pin "10") (pinfunction "PRE_10") (pintype "input"))
      (node (ref "E3") (pin "3") (pinfunction "CLK_3") (pintype "input"))
      (node (ref "IC8") (pin "5") (pinfunction "Y_5") (pintype "output"))
    )
    (net (code "152") (name "RX_SEL") (class "Default")
      (node (ref "E23") (pin "4") (pinfunction "I0_4") (pintype "input"))
      (node (ref "E37") (pin "5") (pinfunction "I0_5") (pintype "input"))
      (node (ref "E37") (pin "6") (pinfunction "I1_6") (pintype "input"))
      (node (ref "E42") (pin "13") (pinfunction "I_13") (pintype "input"))
      (node (ref "IC4") (pin "6") (pinfunction "W_6") (pintype "output"))
    )
    (net (code "153") (name "RX_SEL_L") (class "Default")
      (node (ref "E42") (pin "12") (pinfunction "O_12") (pintype "output"))
      (node (ref "E43") (pin "2") (pinfunction "D_2") (pintype "input"))
    )
    (net (code "154") (name "SELECTED_L") (class "Default")
      (node (ref "E23") (pin "3") (pinfunction "O_3") (pintype "output"))
      (node (ref "E46") (pin "10") (pinfunction "I1_10") (pintype "input"))
      (node (ref "E46") (pin "5") (pinfunction "I1_5") (pintype "input"))
      (node (ref "E46") (pin "6") (pinfunction "I0_6") (pintype "input"))
    )
    (net (code "155") (name "SERIAL_IN") (class "Default")
      (node (ref "E11") (pin "3") (pinfunction "I1_3") (pintype "input"))
      (node (ref "E19") (pin "1") (pinfunction "I0_1") (pintype "input"))
      (node (ref "E21") (pin "9") (pinfunction "I_9") (pintype "input"))
      (node (ref "USB") (pin "3") (pinfunction "3_3") (pintype "passive"))
    )
    (net (code "156") (name "SERIAL_OUT") (class "Default")
      (node (ref "E29") (pin "6") (pinfunction "~{Q}_6") (pintype "output"))
      (node (ref "USB") (pin "2") (pinfunction "2_2") (pintype "passive"))
    )
    (net (code "157") (name "SKIP_L") (class "Default")
      (node (ref "E37") (pin "10") (pinfunction "O_10") (pintype "open_collector"))
      (node (ref "U$2") (pin "CS1") (pinfunction "1_CS1") (pintype "bidirectional"))
    )
    (net (code "158") (name "STP1") (class "Default")
      (node (ref "E23") (pin "6") (pinfunction "I0_6") (pintype "input"))
      (node (ref "E26") (pin "5") (pinfunction "Q0_5") (pintype "output"))
    )
    (net (code "159") (name "STP2") (class "Default")
      (node (ref "E23") (pin "10") (pinfunction "I1_10") (pintype "input"))
      (node (ref "E26") (pin "9") (pinfunction "Q2_9") (pintype "output"))
    )
    (net (code "160") (name "STP_MARK") (class "Default")
      (node (ref "E23") (pin "13") (pinfunction "O_13") (pintype "output"))
      (node (ref "E25") (pin "1") (pinfunction "I4_1") (pintype "input"))
    )
    (net (code "161") (name "SW1") (class "Default")
      (node (ref "IC12") (pin "1") (pinfunction "I0_1") (pintype "input"))
      (node (ref "IC8") (pin "9") (pinfunction "C_9") (pintype "input"))
      (node (ref "RN1") (pin "2") (pinfunction "2_2") (pintype "passive"))
      (node (ref "SW1") (pin "12") (pinfunction "12_12") (pintype "passive"))
    )
    (net (code "162") (name "SW2") (class "Default")
      (node (ref "IC12") (pin "2") (pinfunction "I1_2") (pintype "input"))
      (node (ref "IC8") (pin "10") (pinfunction "B_10") (pintype "input"))
      (node (ref "RN1") (pin "3") (pinfunction "3_3") (pintype "passive"))
      (node (ref "SW1") (pin "11") (pinfunction "11_11") (pintype "passive"))
    )
    (net (code "163") (name "SW3") (class "Default")
      (node (ref "IC12") (pin "13") (pinfunction "I2_13") (pintype "input"))
      (node (ref "IC8") (pin "11") (pinfunction "A_11") (pintype "input"))
      (node (ref "RN1") (pin "4") (pinfunction "4_4") (pintype "passive"))
      (node (ref "SW1") (pin "10") (pinfunction "10_10") (pintype "passive"))
    )
    (net (code "164") (name "SW4") (class "Default")
      (node (ref "IC3") (pin "9") (pinfunction "C_9") (pintype "input"))
      (node (ref "IC4") (pin "9") (pinfunction "C_9") (pintype "input"))
      (node (ref "RN1") (pin "5") (pinfunction "5_5") (pintype "passive"))
      (node (ref "SW1") (pin "9") (pinfunction "9_9") (pintype "passive"))
    )
    (net (code "165") (name "SW5") (class "Default")
      (node (ref "IC3") (pin "10") (pinfunction "B_10") (pintype "input"))
      (node (ref "IC4") (pin "10") (pinfunction "B_10") (pintype "input"))
      (node (ref "RN1") (pin "6") (pinfunction "6_6") (pintype "passive"))
      (node (ref "SW1") (pin "8") (pinfunction "8_8") (pintype "passive"))
    )
    (net (code "166") (name "SW6") (class "Default")
      (node (ref "IC3") (pin "11") (pinfunction "A_11") (pintype "input"))
      (node (ref "IC4") (pin "11") (pinfunction "A_11") (pintype "input"))
      (node (ref "RN1") (pin "7") (pinfunction "7_7") (pintype "passive"))
      (node (ref "SW1") (pin "7") (pinfunction "7_7") (pintype "passive"))
    )
    (net (code "167") (name "TKSKP") (class "Default")
      (node (ref "E39") (pin "4") (pinfunction "I3_4") (pintype "input"))
      (node (ref "E39") (pin "5") (pinfunction "I4_5") (pintype "input"))
      (node (ref "E42") (pin "10") (pinfunction "O_10") (pintype "output"))
    )
    (net (code "168") (name "TP3") (class "Default")
      (node (ref "E34") (pin "9") (pinfunction "I0_9") (pintype "input"))
      (node (ref "U$2") (pin "CH2") (pinfunction "1_CH2") (pintype "bidirectional"))
    )
    (net (code "169") (name "TSKP") (class "Default")
      (node (ref "E45") (pin "13") (pinfunction "O_13") (pintype "output"))
      (node (ref "E45") (pin "6") (pinfunction "I1_6") (pintype "input"))
    )
    (net (code "170") (name "TX7") (class "Default")
      (node (ref "E19") (pin "8") (pinfunction "O_8") (pintype "output"))
      (node (ref "E38") (pin "2") (pinfunction "D_2") (pintype "input"))
    )
    (net (code "171") (name "TX8") (class "Default")
      (node (ref "E19") (pin "6") (pinfunction "O_6") (pintype "output"))
      (node (ref "E25") (pin "10") (pinfunction "I1_10") (pintype "input"))
    )
    (net (code "172") (name "TX_ACTIVE") (class "Default")
      (node (ref "E20") (pin "11") (pinfunction "CLK_11") (pintype "input"))
      (node (ref "E20") (pin "6") (pinfunction "~{Q}_6") (pintype "output"))
      (node (ref "E25") (pin "9") (pinfunction "I2_9") (pintype "input"))
      (node (ref "E29") (pin "4") (pinfunction "PRE_4") (pintype "input"))
      (node (ref "E35") (pin "10") (pinfunction "I1_10") (pintype "input"))
    )
    (net (code "173") (name "TX_DATA") (class "Default")
      (node (ref "E29") (pin "2") (pinfunction "D_2") (pintype "input"))
      (node (ref "E31") (pin "11") (pinfunction "Q3_11") (pintype "output"))
    )
    (net (code "174") (name "TX_DIV") (class "Default")
      (node (ref "E16") (pin "5") (pinfunction "Q_5") (pintype "output"))
      (node (ref "E25") (pin "4") (pinfunction "I3_4") (pintype "input"))
      (node (ref "E26") (pin "1") (pinfunction "R_1") (pintype "input"))
      (node (ref "E29") (pin "3") (pinfunction "CLK_3") (pintype "input"))
      (node (ref "E35") (pin "9") (pinfunction "I0_9") (pintype "input"))
      (node (ref "E38") (pin "3") (pinfunction "CLK_3") (pintype "input"))
    )
    (net (code "175") (name "TX_RATE") (class "Default")
      (node (ref "E1") (pin "3") (pinfunction "O_3") (pintype "output"))
      (node (ref "E16") (pin "3") (pinfunction "CLK_3") (pintype "input"))
      (node (ref "E20") (pin "13") (pinfunction "CLR_13") (pintype "input"))
      (node (ref "E20") (pin "3") (pinfunction "CLK_3") (pintype "input"))
      (node (ref "E21") (pin "5") (pinfunction "I_5") (pintype "input"))
    )
    (net (code "176") (name "TX_SEL") (class "Default")
      (node (ref "E23") (pin "5") (pinfunction "I1_5") (pintype "input"))
      (node (ref "E33") (pin "8") (pinfunction "I0_8") (pintype "input"))
      (node (ref "E33") (pin "9") (pinfunction "I1_9") (pintype "input"))
      (node (ref "E37") (pin "2") (pinfunction "I0_2") (pintype "input"))
      (node (ref "E37") (pin "3") (pinfunction "I1_3") (pintype "input"))
      (node (ref "IC3") (pin "6") (pinfunction "W_6") (pintype "output"))
    )
    (net (code "177") (name "TX_SEL_L") (class "Default")
      (node (ref "E33") (pin "10") (pinfunction "O_10") (pintype "open_collector"))
      (node (ref "E40") (pin "2") (pinfunction "D_2") (pintype "input"))
      (node (ref "R26") (pin "1") (pinfunction "1_1") (pintype "passive"))
    )
    (net (code "178") (name "VCC") (class "Default")
      (node (ref "C1") (pin "1") (pinfunction "1_1") (pintype "passive"))
      (node (ref "C10") (pin "1") (pinfunction "1_1") (pintype "passive"))
      (node (ref "C11") (pin "1") (pinfunction "1_1") (pintype "passive"))
      (node (ref "C12") (pin "1") (pinfunction "1_1") (pintype "passive"))
      (node (ref "C13") (pin "1") (pinfunction "1_1") (pintype "passive"))
      (node (ref "C14") (pin "1") (pinfunction "1_1") (pintype "passive"))
      (node (ref "C15") (pin "1") (pinfunction "1_1") (pintype "passive"))
      (node (ref "C16") (pin "1") (pinfunction "1_1") (pintype "passive"))
      (node (ref "C17") (pin "1") (pinfunction "1_1") (pintype "passive"))
      (node (ref "C18") (pin "1") (pinfunction "1_1") (pintype "passive"))
      (node (ref "C19") (pin "1") (pinfunction "1_1") (pintype "passive"))
      (node (ref "C2") (pin "1") (pinfunction "1_1") (pintype "passive"))
      (node (ref "C20") (pin "1") (pinfunction "1_1") (pintype "passive"))
      (node (ref "C21") (pin "1") (pinfunction "1_1") (pintype "passive"))
      (node (ref "C22") (pin "1") (pinfunction "1_1") (pintype "passive"))
      (node (ref "C23") (pin "1") (pinfunction "1_1") (pintype "passive"))
      (node (ref "C24") (pin "1") (pinfunction "1_1") (pintype "passive"))
      (node (ref "C25") (pin "1") (pinfunction "1_1") (pintype "passive"))
      (node (ref "C26") (pin "1") (pinfunction "1_1") (pintype "passive"))
      (node (ref "C27") (pin "1") (pinfunction "1_1") (pintype "passive"))
      (node (ref "C28") (pin "1") (pinfunction "1_1") (pintype "passive"))
      (node (ref "C29") (pin "1") (pinfunction "1_1") (pintype "passive"))
      (node (ref "C3") (pin "1") (pinfunction "1_1") (pintype "passive"))
      (node (ref "C30") (pin "1") (pinfunction "1_1") (pintype "passive"))
      (node (ref "C31") (pin "1") (pinfunction "1_1") (pintype "passive"))
      (node (ref "C33") (pin "1") (pinfunction "1_1") (pintype "passive"))
      (node (ref "C34") (pin "1") (pinfunction "1_1") (pintype "passive"))
      (node (ref "C35") (pin "1") (pinfunction "1_1") (pintype "passive"))
      (node (ref "C36") (pin "1") (pinfunction "1_1") (pintype "passive"))
      (node (ref "C37") (pin "1") (pinfunction "1_1") (pintype "passive"))
      (node (ref "C38") (pin "1") (pinfunction "1_1") (pintype "passive"))
      (node (ref "C39") (pin "1") (pinfunction "1_1") (pintype "passive"))
      (node (ref "C4") (pin "1") (pinfunction "1_1") (pintype "passive"))
      (node (ref "C40") (pin "1") (pinfunction "1_1") (pintype "passive"))
      (node (ref "C41") (pin "1") (pinfunction "1_1") (pintype "passive"))
      (node (ref "C42") (pin "1") (pinfunction "1_1") (pintype "passive"))
      (node (ref "C43") (pin "1") (pinfunction "1_1") (pintype "passive"))
      (node (ref "C44") (pin "1") (pinfunction "1_1") (pintype "passive"))
      (node (ref "C45") (pin "1") (pinfunction "1_1") (pintype "passive"))
      (node (ref "C46") (pin "1") (pinfunction "1_1") (pintype "passive"))
      (node (ref "C47") (pin "1") (pinfunction "1_1") (pintype "passive"))
      (node (ref "C48") (pin "1") (pinfunction "1_1") (pintype "passive"))
      (node (ref "C5") (pin "1") (pinfunction "1_1") (pintype "passive"))
      (node (ref "C51") (pin "+") (pinfunction "+_+") (pintype "passive"))
      (node (ref "C52") (pin "+") (pinfunction "+_+") (pintype "passive"))
      (node (ref "C53") (pin "+") (pinfunction "+_+") (pintype "passive"))
      (node (ref "C56") (pin "+") (pinfunction "+_+") (pintype "passive"))
      (node (ref "C57") (pin "1") (pinfunction "1_1") (pintype "passive"))
      (node (ref "C6") (pin "1") (pinfunction "1_1") (pintype "passive"))
      (node (ref "C7") (pin "1") (pinfunction "1_1") (pintype "passive"))
      (node (ref "C8") (pin "1") (pinfunction "1_1") (pintype "passive"))
      (node (ref "C9") (pin "1") (pinfunction "1_1") (pintype "passive"))
      (node (ref "IC3") (pin "4") (pinfunction "D0_4") (pintype "input"))
      (node (ref "IC4") (pin "4") (pinfunction "D0_4") (pintype "input"))
      (node (ref "OSC") (pin "8") (pinfunction "VCC_8") (pintype "power_in"))
      (node (ref "OSC1") (pin "14") (pinfunction "VCC_14") (pintype "power_in"))
      (node (ref "R1") (pin "2") (pinfunction "2_2") (pintype "passive"))
      (node (ref "R10") (pin "2") (pinfunction "2_2") (pintype "passive"))
      (node (ref "R15") (pin "2") (pinfunction "2_2") (pintype "passive"))
      (node (ref "R21") (pin "2") (pinfunction "2_2") (pintype "passive"))
      (node (ref "R24") (pin "2") (pinfunction "2_2") (pintype "passive"))
      (node (ref "R26") (pin "2") (pinfunction "2_2") (pintype "passive"))
      (node (ref "RN1") (pin "1") (pinfunction "1_1") (pintype "passive"))
      (node (ref "U$2") (pin "AA2") (pinfunction "1_AA2") (pintype "bidirectional"))
      (node (ref "U$2") (pin "BA2") (pinfunction "1_BA2") (pintype "bidirectional"))
      (node (ref "U$2") (pin "CA2") (pinfunction "1_CA2") (pintype "bidirectional"))
    )
    (net (code "179") (name "unconnected-(E3B-Q-Pad9)") (class "Default")
      (node (ref "E3") (pin "9") (pinfunction "Q_9") (pintype "output"))
    )
    (net (code "180") (name "unconnected-(E4A-Q-Pad5)") (class "Default")
      (node (ref "E4") (pin "5") (pinfunction "Q_5") (pintype "output"))
    )
    (net (code "181") (name "unconnected-(E4B-Q-Pad9)") (class "Default")
      (node (ref "E4") (pin "9") (pinfunction "Q_9") (pintype "output"))
    )
    (net (code "182") (name "unconnected-(E5A-QC-Pad8)") (class "Default")
      (node (ref "E5") (pin "8") (pinfunction "QC_8") (pintype "output"))
    )
    (net (code "183") (name "unconnected-(E6A-Q4-Pad12)") (class "Default")
      (node (ref "E6") (pin "12") (pinfunction "Q4_12") (pintype "output"))
    )
    (net (code "184") (name "unconnected-(E7B-~{Q}-Pad8)") (class "Default")
      (node (ref "E7") (pin "8") (pinfunction "~{Q}_8") (pintype "output"))
    )
    (net (code "185") (name "unconnected-(E16B-Q-Pad9)") (class "Default")
      (node (ref "E16") (pin "9") (pinfunction "Q_9") (pintype "output"))
    )
    (net (code "186") (name "unconnected-(E18A-QB-Pad9)") (class "Default")
      (node (ref "E18") (pin "9") (pinfunction "QB_9") (pintype "output"))
    )
    (net (code "187") (name "unconnected-(E18A-QC-Pad8)") (class "Default")
      (node (ref "E18") (pin "8") (pinfunction "QC_8") (pintype "output"))
    )
    (net (code "188") (name "unconnected-(E18A-QD-Pad11)") (class "Default")
      (node (ref "E18") (pin "11") (pinfunction "QD_11") (pintype "output"))
    )
    (net (code "189") (name "unconnected-(E20B-Q-Pad9)") (class "Default")
      (node (ref "E20") (pin "9") (pinfunction "Q_9") (pintype "output"))
    )
    (net (code "190") (name "unconnected-(E25A-I5-Pad12)") (class "Default")
      (node (ref "E25") (pin "12") (pinfunction "I5_12") (pintype "passive"))
    )
    (net (code "191") (name "unconnected-(E25A-I6-Pad11)") (class "Default")
      (node (ref "E25") (pin "11") (pinfunction "I6_11") (pintype "passive"))
    )
    (net (code "192") (name "unconnected-(E26A-I0-Pad3)") (class "Default")
      (node (ref "E26") (pin "3") (pinfunction "I0_3") (pintype "input"))
    )
    (net (code "193") (name "unconnected-(E26A-I1-Pad2)") (class "Default")
      (node (ref "E26") (pin "2") (pinfunction "I1_2") (pintype "input"))
    )
    (net (code "194") (name "unconnected-(E26A-I2-Pad15)") (class "Default")
      (node (ref "E26") (pin "15") (pinfunction "I2_15") (pintype "input"))
    )
    (net (code "195") (name "unconnected-(E26A-I3-Pad14)") (class "Default")
      (node (ref "E26") (pin "14") (pinfunction "I3_14") (pintype "input"))
    )
    (net (code "196") (name "unconnected-(E26A-Q1-Pad7)") (class "Default")
      (node (ref "E26") (pin "7") (pinfunction "Q1_7") (pintype "output"))
    )
    (net (code "197") (name "unconnected-(E26A-Q3-Pad11)") (class "Default")
      (node (ref "E26") (pin "11") (pinfunction "Q3_11") (pintype "output"))
    )
    (net (code "198") (name "unconnected-(E26A-Q4-Pad12)") (class "Default")
      (node (ref "E26") (pin "12") (pinfunction "Q4_12") (pintype "output"))
    )
    (net (code "199") (name "unconnected-(E28A-Q4-Pad12)") (class "Default")
      (node (ref "E28") (pin "12") (pinfunction "Q4_12") (pintype "output"))
    )
    (net (code "200") (name "unconnected-(E29A-Q-Pad5)") (class "Default")
      (node (ref "E29") (pin "5") (pinfunction "Q_5") (pintype "output"))
    )
    (net (code "201") (name "unconnected-(E29B-~{Q}-Pad8)") (class "Default")
      (node (ref "E29") (pin "8") (pinfunction "~{Q}_8") (pintype "output"))
    )
    (net (code "202") (name "unconnected-(E31A-Q4-Pad12)") (class "Default")
      (node (ref "E31") (pin "12") (pinfunction "Q4_12") (pintype "output"))
    )
    (net (code "203") (name "unconnected-(E38A-~{Q}-Pad6)") (class "Default")
      (node (ref "E38") (pin "6") (pinfunction "~{Q}_6") (pintype "output"))
    )
    (net (code "204") (name "unconnected-(E39A-I5-Pad12)") (class "Default")
      (node (ref "E39") (pin "12") (pinfunction "I5_12") (pintype "passive"))
    )
    (net (code "205") (name "unconnected-(E39A-I6-Pad11)") (class "Default")
      (node (ref "E39") (pin "11") (pinfunction "I6_11") (pintype "passive"))
    )
    (net (code "206") (name "unconnected-(E40A-3-Pad10)") (class "Default")
      (node (ref "E40") (pin "10") (pinfunction "3_10") (pintype "output"))
    )
    (net (code "207") (name "unconnected-(E40A-7-Pad5)") (class "Default")
      (node (ref "E40") (pin "5") (pinfunction "7_5") (pintype "output"))
    )
    (net (code "208") (name "unconnected-(E40A-8-Pad6)") (class "Default")
      (node (ref "E40") (pin "6") (pinfunction "8_6") (pintype "output"))
    )
    (net (code "209") (name "unconnected-(E40A-9-Pad7)") (class "Default")
      (node (ref "E40") (pin "7") (pinfunction "9_7") (pintype "output"))
    )
    (net (code "210") (name "unconnected-(E43A-3-Pad10)") (class "Default")
      (node (ref "E43") (pin "10") (pinfunction "3_10") (pintype "output"))
    )
    (net (code "211") (name "unconnected-(E43A-7-Pad5)") (class "Default")
      (node (ref "E43") (pin "5") (pinfunction "7_5") (pintype "output"))
    )
    (net (code "212") (name "unconnected-(E43A-8-Pad6)") (class "Default")
      (node (ref "E43") (pin "6") (pinfunction "8_6") (pintype "output"))
    )
    (net (code "213") (name "unconnected-(E43A-9-Pad7)") (class "Default")
      (node (ref "E43") (pin "7") (pinfunction "9_7") (pintype "output"))
    )
    (net (code "214") (name "unconnected-(E48A-Q-Pad5)") (class "Default")
      (node (ref "E48") (pin "5") (pinfunction "Q_5") (pintype "output"))
    )
    (net (code "215") (name "unconnected-(E48B-~{Q}-Pad8)") (class "Default")
      (node (ref "E48") (pin "8") (pinfunction "~{Q}_8") (pintype "output"))
    )
    (net (code "216") (name "unconnected-(IC1A-Y0-Pad15)") (class "Default")
      (node (ref "IC1") (pin "15") (pinfunction "Y0_15") (pintype "output"))
    )
    (net (code "217") (name "unconnected-(IC1A-Y1-Pad14)") (class "Default")
      (node (ref "IC1") (pin "14") (pinfunction "Y1_14") (pintype "output"))
    )
    (net (code "218") (name "unconnected-(IC1A-Y2-Pad13)") (class "Default")
      (node (ref "IC1") (pin "13") (pinfunction "Y2_13") (pintype "output"))
    )
    (net (code "219") (name "unconnected-(IC1A-Y5-Pad10)") (class "Default")
      (node (ref "IC1") (pin "10") (pinfunction "Y5_10") (pintype "output"))
    )
    (net (code "220") (name "unconnected-(IC3A-Y-Pad5)") (class "Default")
      (node (ref "IC3") (pin "5") (pinfunction "Y_5") (pintype "output"))
    )
    (net (code "221") (name "unconnected-(IC4A-Y-Pad5)") (class "Default")
      (node (ref "IC4") (pin "5") (pinfunction "Y_5") (pintype "output"))
    )
    (net (code "222") (name "unconnected-(IC5A-Y0-Pad15)") (class "Default")
      (node (ref "IC5") (pin "15") (pinfunction "Y0_15") (pintype "output"))
    )
    (net (code "223") (name "unconnected-(IC5A-Y1-Pad14)") (class "Default")
      (node (ref "IC5") (pin "14") (pinfunction "Y1_14") (pintype "output"))
    )
    (net (code "224") (name "unconnected-(IC5A-Y2-Pad13)") (class "Default")
      (node (ref "IC5") (pin "13") (pinfunction "Y2_13") (pintype "output"))
    )
    (net (code "225") (name "unconnected-(IC5A-Y5-Pad10)") (class "Default")
      (node (ref "IC5") (pin "10") (pinfunction "Y5_10") (pintype "output"))
    )
    (net (code "226") (name "unconnected-(IC5A-Y6-Pad9)") (class "Default")
      (node (ref "IC5") (pin "9") (pinfunction "Y6_9") (pintype "output"))
    )
    (net (code "227") (name "unconnected-(IC5A-Y7-Pad7)") (class "Default")
      (node (ref "IC5") (pin "7") (pinfunction "Y7_7") (pintype "output"))
    )
    (net (code "228") (name "unconnected-(IC6A-Y0-Pad15)") (class "Default")
      (node (ref "IC6") (pin "15") (pinfunction "Y0_15") (pintype "output"))
    )
    (net (code "229") (name "unconnected-(IC6A-Y1-Pad14)") (class "Default")
      (node (ref "IC6") (pin "14") (pinfunction "Y1_14") (pintype "output"))
    )
    (net (code "230") (name "unconnected-(IC6A-Y2-Pad13)") (class "Default")
      (node (ref "IC6") (pin "13") (pinfunction "Y2_13") (pintype "output"))
    )
    (net (code "231") (name "unconnected-(IC6A-Y3-Pad12)") (class "Default")
      (node (ref "IC6") (pin "12") (pinfunction "Y3_12") (pintype "output"))
    )
    (net (code "232") (name "unconnected-(IC6A-Y4-Pad11)") (class "Default")
      (node (ref "IC6") (pin "11") (pinfunction "Y4_11") (pintype "output"))
    )
    (net (code "233") (name "unconnected-(IC6A-Y7-Pad7)") (class "Default")
      (node (ref "IC6") (pin "7") (pinfunction "Y7_7") (pintype "output"))
    )
    (net (code "234") (name "unconnected-(IC7A-Y0-Pad15)") (class "Default")
      (node (ref "IC7") (pin "15") (pinfunction "Y0_15") (pintype "output"))
    )
    (net (code "235") (name "unconnected-(IC7A-Y1-Pad14)") (class "Default")
      (node (ref "IC7") (pin "14") (pinfunction "Y1_14") (pintype "output"))
    )
    (net (code "236") (name "unconnected-(IC7A-Y4-Pad11)") (class "Default")
      (node (ref "IC7") (pin "11") (pinfunction "Y4_11") (pintype "output"))
    )
    (net (code "237") (name "unconnected-(IC7A-Y5-Pad10)") (class "Default")
      (node (ref "IC7") (pin "10") (pinfunction "Y5_10") (pintype "output"))
    )
    (net (code "238") (name "unconnected-(IC7A-Y6-Pad9)") (class "Default")
      (node (ref "IC7") (pin "9") (pinfunction "Y6_9") (pintype "output"))
    )
    (net (code "239") (name "unconnected-(IC7A-Y7-Pad7)") (class "Default")
      (node (ref "IC7") (pin "7") (pinfunction "Y7_7") (pintype "output"))
    )
    (net (code "240") (name "unconnected-(RN1-Pad8)") (class "Default")
      (node (ref "RN1") (pin "8") (pinfunction "8_8") (pintype "passive"))
    )
    (net (code "241") (name "unconnected-(RN1-Pad9)") (class "Default")
      (node (ref "RN1") (pin "9") (pinfunction "9_9") (pintype "passive"))
    )
    (net (code "242") (name "unconnected-(RN1-Pad10)") (class "Default")
      (node (ref "RN1") (pin "10") (pinfunction "10_10") (pintype "passive"))
    )
    (net (code "243") (name "unconnected-(USB-Pad1)") (class "Default")
      (node (ref "USB") (pin "1") (pinfunction "1_1") (pintype "passive"))
    )
    (net (code "244") (name "unconnected-(USB-Pad4)") (class "Default")
      (node (ref "USB") (pin "4") (pinfunction "4_4") (pintype "passive"))
    )
    (net (code "245") (name "unconnected-(USB-Pad6)") (class "Default")
      (node (ref "USB") (pin "6") (pinfunction "6_6") (pintype "passive"))
    )
    (net (code "246") (name "unconnected-(USB-Pad7)") (class "Default")
      (node (ref "USB") (pin "7") (pinfunction "7_7") (pintype "passive"))
    )
    (net (code "247") (name "unconnected-(USB-Pad8)") (class "Default")
      (node (ref "USB") (pin "8") (pinfunction "8_8") (pintype "passive"))
    )
    (net (code "248") (name "unconnected-(USB-Pad9)") (class "Default")
      (node (ref "USB") (pin "9") (pinfunction "9_9") (pintype "passive"))
    )
    (net (code "249") (name "~{CKKCC}") (class "Default")
      (node (ref "E35") (pin "4") (pinfunction "I0_4") (pintype "input"))
      (node (ref "E44") (pin "11") (pinfunction "O_11") (pintype "output"))
      (node (ref "E48") (pin "13") (pinfunction "CLR_13") (pintype "input"))
    )
    (net (code "250") (name "~{CKTFL}") (class "Default")
      (node (ref "E38") (pin "1") (pinfunction "CLR_1") (pintype "input"))
      (node (ref "E42") (pin "2") (pinfunction "O_2") (pintype "output"))
    )
    (net (code "251") (name "~{DOTPC}") (class "Default")
      (node (ref "E27") (pin "10") (pinfunction "I1_10") (pintype "input"))
      (node (ref "E27") (pin "11") (pinfunction "I0_11") (pintype "input"))
      (node (ref "E27") (pin "5") (pinfunction "I1_5") (pintype "input"))
      (node (ref "E27") (pin "6") (pinfunction "I0_6") (pintype "input"))
      (node (ref "E28") (pin "13") (pinfunction "S_13") (pintype "input"))
      (node (ref "E30") (pin "10") (pinfunction "I1_10") (pintype "input"))
      (node (ref "E30") (pin "11") (pinfunction "I0_11") (pintype "input"))
      (node (ref "E30") (pin "5") (pinfunction "I1_5") (pintype "input"))
      (node (ref "E30") (pin "6") (pinfunction "I0_6") (pintype "input"))
      (node (ref "E31") (pin "13") (pinfunction "S_13") (pintype "input"))
      (node (ref "E35") (pin "3") (pinfunction "O_3") (pintype "output"))
      (node (ref "R10") (pin "1") (pinfunction "1_1") (pintype "passive"))
    )
    (net (code "252") (name "~{INIT}") (class "Default")
      (node (ref "E16") (pin "13") (pinfunction "CLR_13") (pintype "input"))
      (node (ref "E16") (pin "4") (pinfunction "PRE_4") (pintype "input"))
      (node (ref "E29") (pin "13") (pinfunction "CLR_13") (pintype "input"))
      (node (ref "E46") (pin "13") (pinfunction "O_13") (pintype "output"))
      (node (ref "E48") (pin "10") (pinfunction "PRE_10") (pintype "input"))
    )
    (net (code "253") (name "~{INT_ENAB}") (class "Default")
      (node (ref "E38") (pin "9") (pinfunction "Q_9") (pintype "output"))
      (node (ref "E45") (pin "9") (pinfunction "I1_9") (pintype "input"))
    )
    (net (code "254") (name "~{KCC}") (class "Default")
      (node (ref "E43") (pin "11") (pinfunction "2_11") (pintype "output"))
      (node (ref "E44") (pin "10") (pinfunction "I1_10") (pintype "input"))
    )
    (net (code "255") (name "~{KCF}") (class "Default")
      (node (ref "E43") (pin "13") (pinfunction "0_13") (pintype "output"))
      (node (ref "E47") (pin "6") (pinfunction "I1_6") (pintype "input"))
    )
    (net (code "256") (name "~{KIE}") (class "Default")
      (node (ref "E43") (pin "3") (pinfunction "5_3") (pintype "output"))
      (node (ref "E47") (pin "8") (pinfunction "I0_8") (pintype "input"))
    )
    (net (code "257") (name "~{KRB}") (class "Default")
      (node (ref "E43") (pin "4") (pinfunction "6_4") (pintype "output"))
      (node (ref "E44") (pin "4") (pinfunction "I0_4") (pintype "input"))
      (node (ref "E44") (pin "9") (pinfunction "I0_9") (pintype "input"))
    )
    (net (code "258") (name "~{KRS}") (class "Default")
      (node (ref "E43") (pin "9") (pinfunction "4_9") (pintype "output"))
      (node (ref "E44") (pin "5") (pinfunction "I1_5") (pintype "input"))
    )
    (net (code "259") (name "~{KSF}") (class "Default")
      (node (ref "E43") (pin "12") (pinfunction "1_12") (pintype "output"))
      (node (ref "E47") (pin "11") (pinfunction "I0_11") (pintype "input"))
    )
    (net (code "260") (name "~{LAST_UNIT}") (class "Default")
      (node (ref "E12") (pin "12") (pinfunction "I0_12") (pintype "input"))
      (node (ref "E8") (pin "6") (pinfunction "~{Q}_6") (pintype "output"))
    )
    (net (code "261") (name "~{P_PULSE}") (class "Default")
      (node (ref "E10") (pin "13") (pinfunction "S_13") (pintype "input"))
      (node (ref "E11") (pin "8") (pinfunction "I0_8") (pintype "input"))
      (node (ref "E6") (pin "13") (pinfunction "S_13") (pintype "input"))
      (node (ref "E7") (pin "9") (pinfunction "Q_9") (pintype "output"))
    )
    (net (code "262") (name "~{RFLG}") (class "Default")
      (node (ref "E44") (pin "1") (pinfunction "I0_1") (pintype "input"))
      (node (ref "E47") (pin "12") (pinfunction "I1_12") (pintype "input"))
      (node (ref "E48") (pin "6") (pinfunction "~{Q}_6") (pintype "output"))
    )
    (net (code "263") (name "~{RX_ACTIVE8}") (class "Default")
      (node (ref "E11") (pin "11") (pinfunction "I0_11") (pintype "input"))
      (node (ref "E11") (pin "12") (pinfunction "I1_12") (pintype "input"))
      (node (ref "E12") (pin "3") (pinfunction "O_3") (pintype "output"))
      (node (ref "E16") (pin "11") (pinfunction "CLK_11") (pintype "input"))
      (node (ref "E39") (pin "1") (pinfunction "I4_1") (pintype "input"))
    )
    (net (code "264") (name "~{RX_ACTIVE}") (class "Default")
      (node (ref "E12") (pin "13") (pinfunction "I1_13") (pintype "input"))
      (node (ref "E12") (pin "4") (pinfunction "I0_4") (pintype "input"))
      (node (ref "E7") (pin "6") (pinfunction "~{Q}_6") (pintype "output"))
    )
    (net (code "265") (name "~{RX_AGAIN}") (class "Default")
      (node (ref "E16") (pin "10") (pinfunction "PRE_10") (pintype "input"))
      (node (ref "E19") (pin "12") (pinfunction "O_12") (pintype "output"))
      (node (ref "E7") (pin "4") (pinfunction "PRE_4") (pintype "input"))
    )
    (net (code "266") (name "~{RX_DIV2}") (class "Default")
      (node (ref "E11") (pin "9") (pinfunction "I1_9") (pintype "input"))
      (node (ref "E4") (pin "11") (pinfunction "CLK_11") (pintype "input"))
      (node (ref "E4") (pin "2") (pinfunction "D_2") (pintype "input"))
      (node (ref "E4") (pin "6") (pinfunction "~{Q}_6") (pintype "output"))
    )
    (net (code "267") (name "~{RX_DIV4}") (class "Default")
      (node (ref "E4") (pin "12") (pinfunction "D_12") (pintype "input"))
      (node (ref "E4") (pin "8") (pinfunction "~{Q}_8") (pintype "output"))
      (node (ref "E7") (pin "10") (pinfunction "PRE_10") (pintype "input"))
      (node (ref "E8") (pin "11") (pinfunction "CLK_11") (pintype "input"))
    )
    (net (code "268") (name "~{RX_DIV}") (class "Default")
      (node (ref "E3") (pin "6") (pinfunction "~{Q}_6") (pintype "output"))
      (node (ref "E4") (pin "3") (pinfunction "CLK_3") (pintype "input"))
    )
    (net (code "269") (name "~{RX_LAST}") (class "Default")
      (node (ref "E12") (pin "10") (pinfunction "I1_10") (pintype "input"))
      (node (ref "E12") (pin "11") (pinfunction "O_11") (pintype "output"))
      (node (ref "E21") (pin "11") (pinfunction "I_11") (pintype "input"))
      (node (ref "E36") (pin "4") (pinfunction "I0_4") (pintype "input"))
      (node (ref "E36") (pin "5") (pinfunction "I1_5") (pintype "input"))
      (node (ref "R15") (pin "1") (pinfunction "1_1") (pintype "passive"))
    )
    (net (code "270") (name "~{R_RUN}") (class "Default")
      (node (ref "E48") (pin "9") (pinfunction "Q_9") (pintype "output"))
      (node (ref "U$2") (pin "DB1") (pinfunction "1_DB1") (pintype "bidirectional"))
    )
    (net (code "271") (name "~{SPIKE_DET}") (class "Default")
      (node (ref "E11") (pin "2") (pinfunction "I0_2") (pintype "input"))
      (node (ref "E16") (pin "8") (pinfunction "~{Q}_8") (pintype "output"))
    )
    (net (code "272") (name "~{START}") (class "Default")
      (node (ref "E20") (pin "8") (pinfunction "~{Q}_8") (pintype "output"))
      (node (ref "E29") (pin "1") (pinfunction "CLR_1") (pintype "input"))
    )
    (net (code "273") (name "~{TCF}") (class "Default")
      (node (ref "E40") (pin "11") (pinfunction "2_11") (pintype "output"))
      (node (ref "E41") (pin "10") (pinfunction "I1_10") (pintype "input"))
    )
    (net (code "274") (name "~{TFLG}") (class "Default")
      (node (ref "E38") (pin "5") (pinfunction "Q_5") (pintype "output"))
      (node (ref "E44") (pin "2") (pinfunction "I1_2") (pintype "input"))
      (node (ref "E45") (pin "11") (pinfunction "I0_11") (pintype "input"))
    )
    (net (code "275") (name "~{TFL}") (class "Default")
      (node (ref "E40") (pin "13") (pinfunction "0_13") (pintype "output"))
      (node (ref "E45") (pin "2") (pinfunction "I0_2") (pintype "input"))
    )
    (net (code "276") (name "~{TLS}") (class "Default")
      (node (ref "E40") (pin "4") (pinfunction "6_4") (pintype "output"))
      (node (ref "E41") (pin "4") (pinfunction "I0_4") (pintype "input"))
      (node (ref "E41") (pin "9") (pinfunction "I0_9") (pintype "input"))
    )
    (net (code "277") (name "~{TP3}") (class "Default")
      (node (ref "E42") (pin "4") (pinfunction "O_4") (pintype "output"))
      (node (ref "E45") (pin "3") (pinfunction "I1_3") (pintype "input"))
      (node (ref "E47") (pin "5") (pinfunction "I0_5") (pintype "input"))
      (node (ref "E47") (pin "9") (pinfunction "I1_9") (pintype "input"))
    )
    (net (code "278") (name "~{TPC}") (class "Default")
      (node (ref "E40") (pin "9") (pinfunction "4_9") (pintype "output"))
      (node (ref "E41") (pin "5") (pinfunction "I1_5") (pintype "input"))
    )
    (net (code "279") (name "~{TSF}") (class "Default")
      (node (ref "E40") (pin "12") (pinfunction "1_12") (pintype "output"))
      (node (ref "E45") (pin "12") (pinfunction "I1_12") (pintype "input"))
    )
    (net (code "280") (name "~{TSK}") (class "Default")
      (node (ref "E40") (pin "3") (pinfunction "5_3") (pintype "output"))
      (node (ref "E45") (pin "8") (pinfunction "I0_8") (pintype "input"))
    )
    (net (code "281") (name "~{TX_ACTIVE}") (class "Default")
      (node (ref "E20") (pin "5") (pinfunction "Q_5") (pintype "output"))
      (node (ref "E26") (pin "4") (pinfunction "D_4") (pintype "input"))
    )
    (net (code "282") (name "~{TX_DIV}") (class "Default")
      (node (ref "DL1") (pin "1") (pinfunction "1_1") (pintype "passive"))
      (node (ref "E16") (pin "6") (pinfunction "~{Q}_6") (pintype "output"))
      (node (ref "E19") (pin "4") (pinfunction "I1_4") (pintype "input"))
      (node (ref "R21") (pin "1") (pinfunction "1_1") (pintype "passive"))
    )
    (net (code "283") (name "~{TX_SHIFT}") (class "Default")
      (node (ref "E21") (pin "3") (pinfunction "I_3") (pintype "input"))
      (node (ref "E25") (pin "6") (pinfunction "O_6") (pintype "output"))
      (node (ref "E28") (pin "6") (pinfunction "C_6") (pintype "input"))
      (node (ref "E31") (pin "6") (pinfunction "C_6") (pintype "input"))
    )
  )
)
